# Schematic.net
KiCad netlist of a schematic drawn in EAGLE
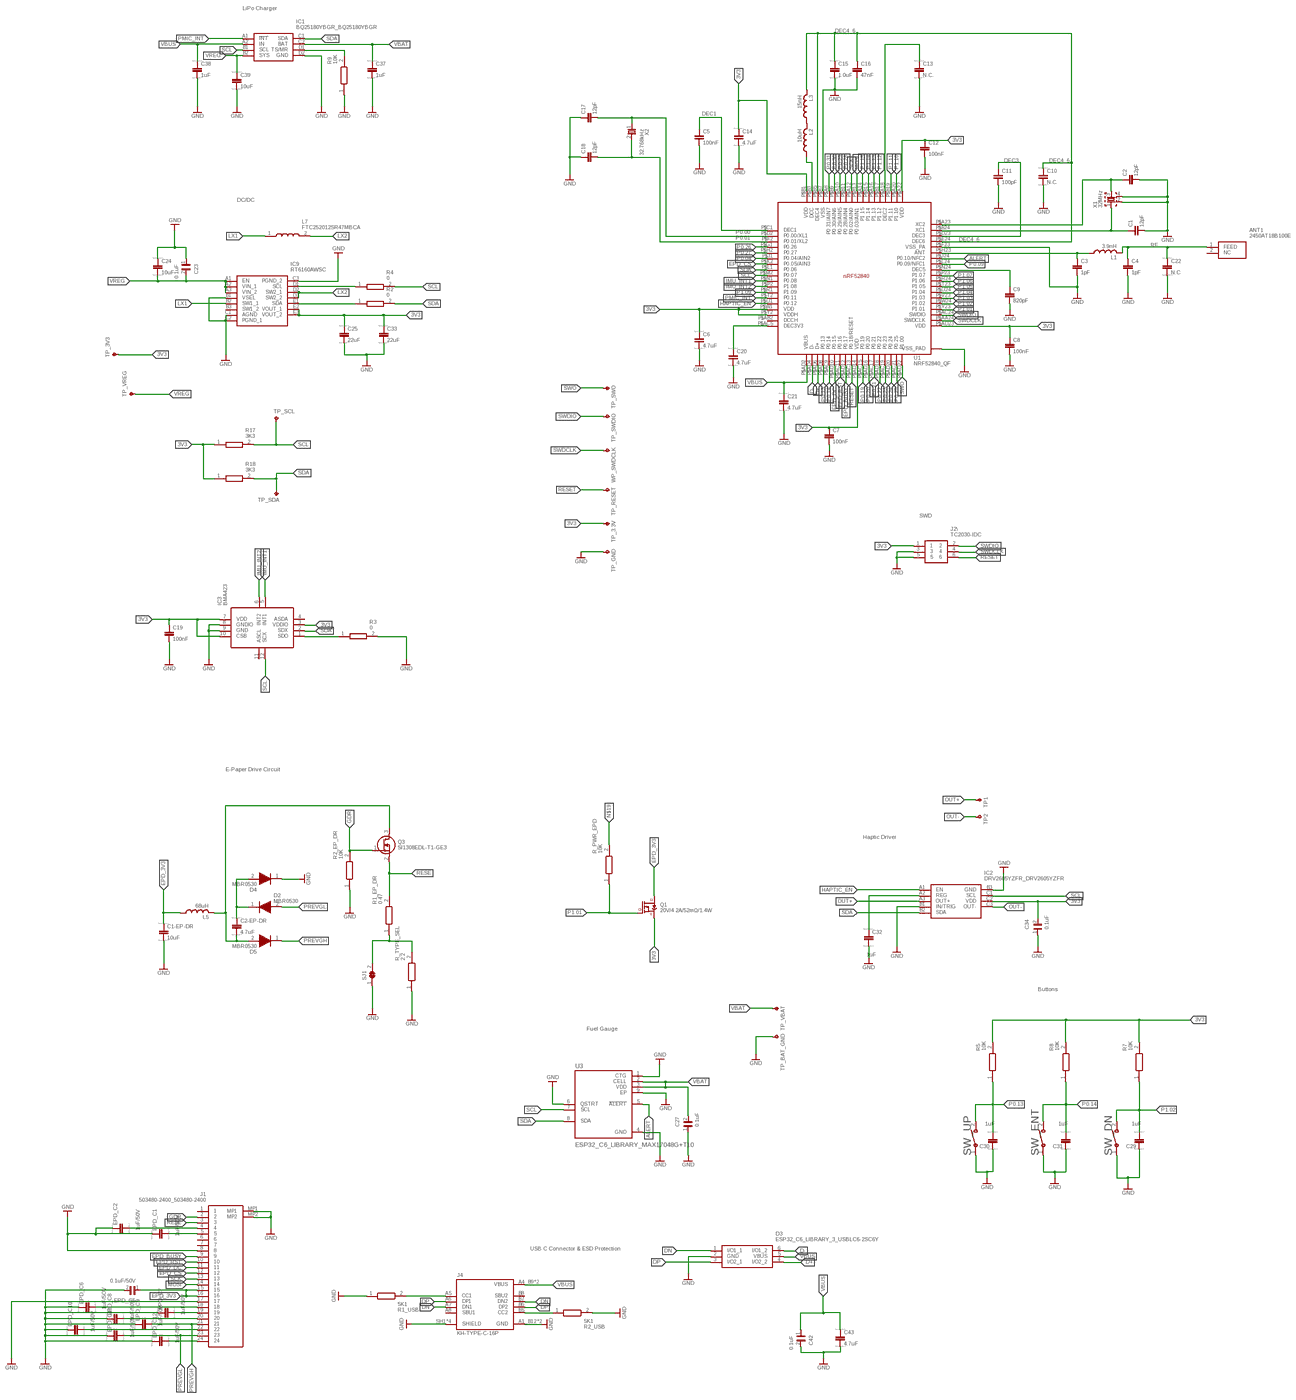
[diagram p0: schematic, sheet 1, overview]
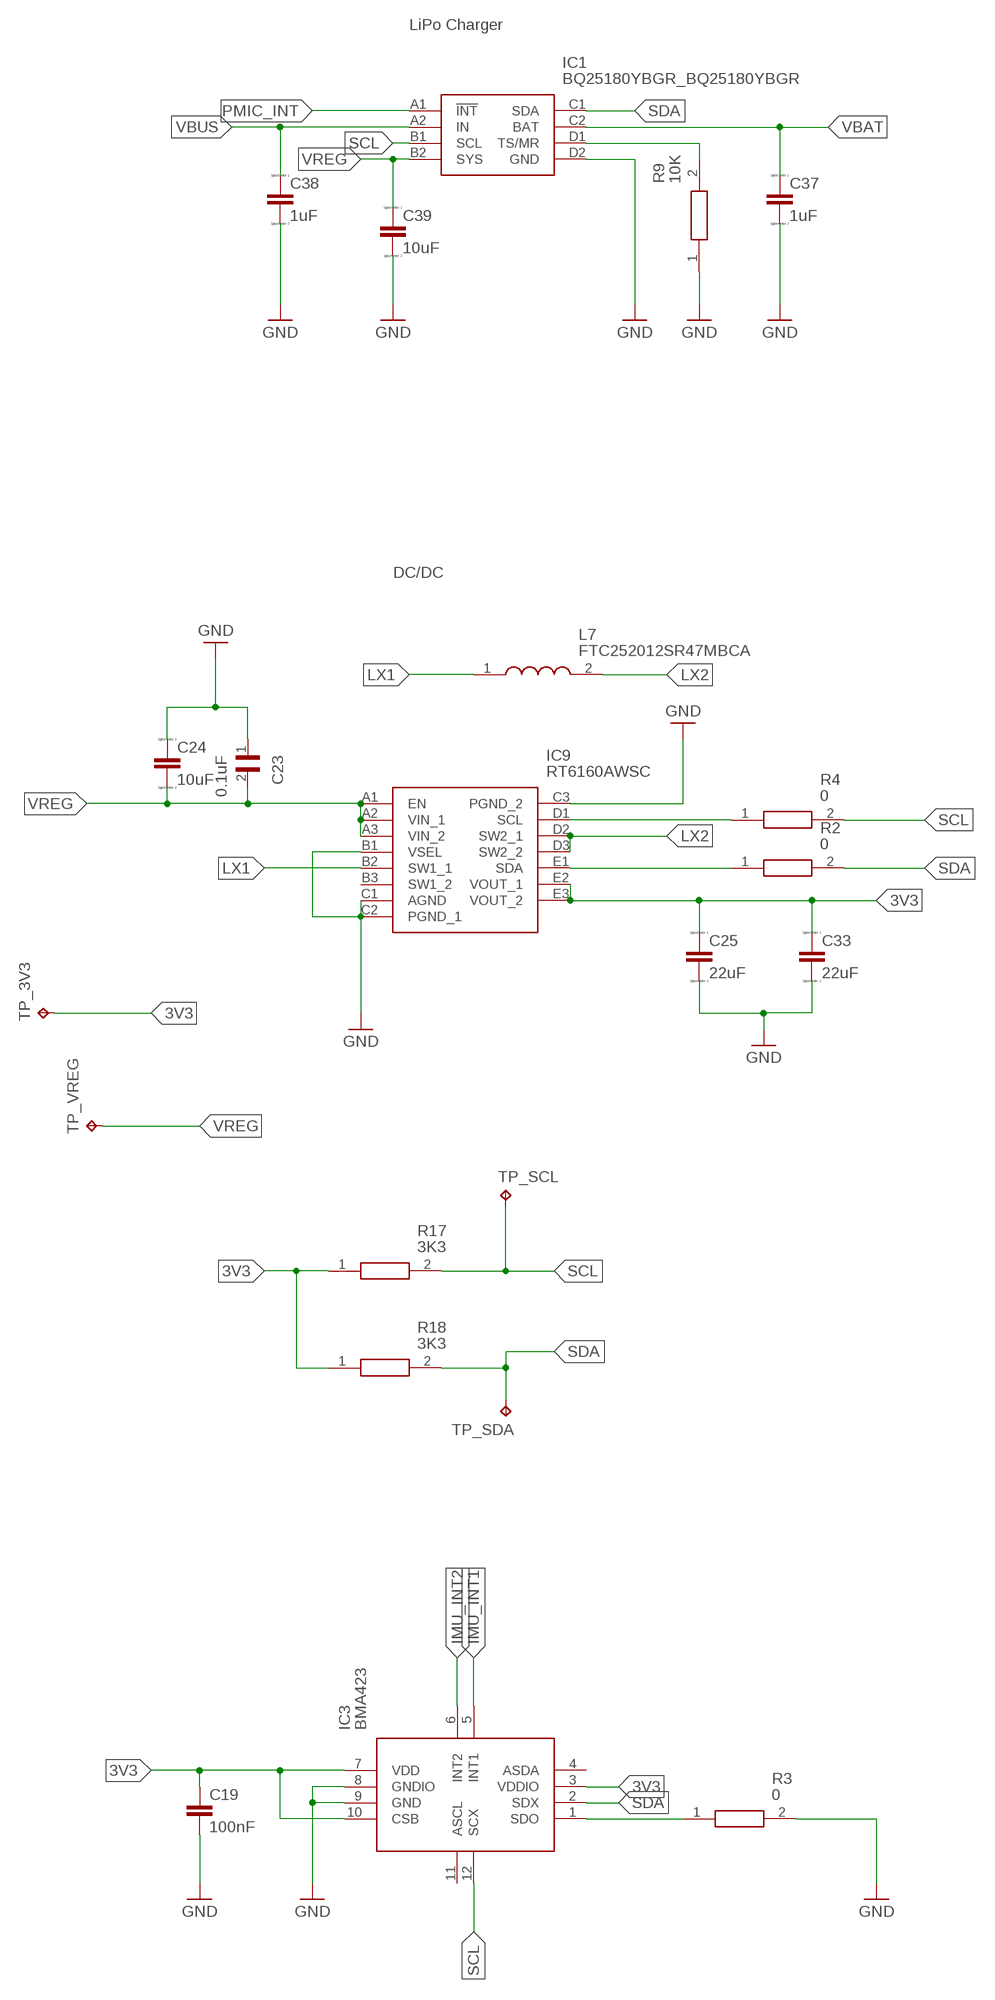
[diagram p1: schematic, sheet 1, part 1 of 4]
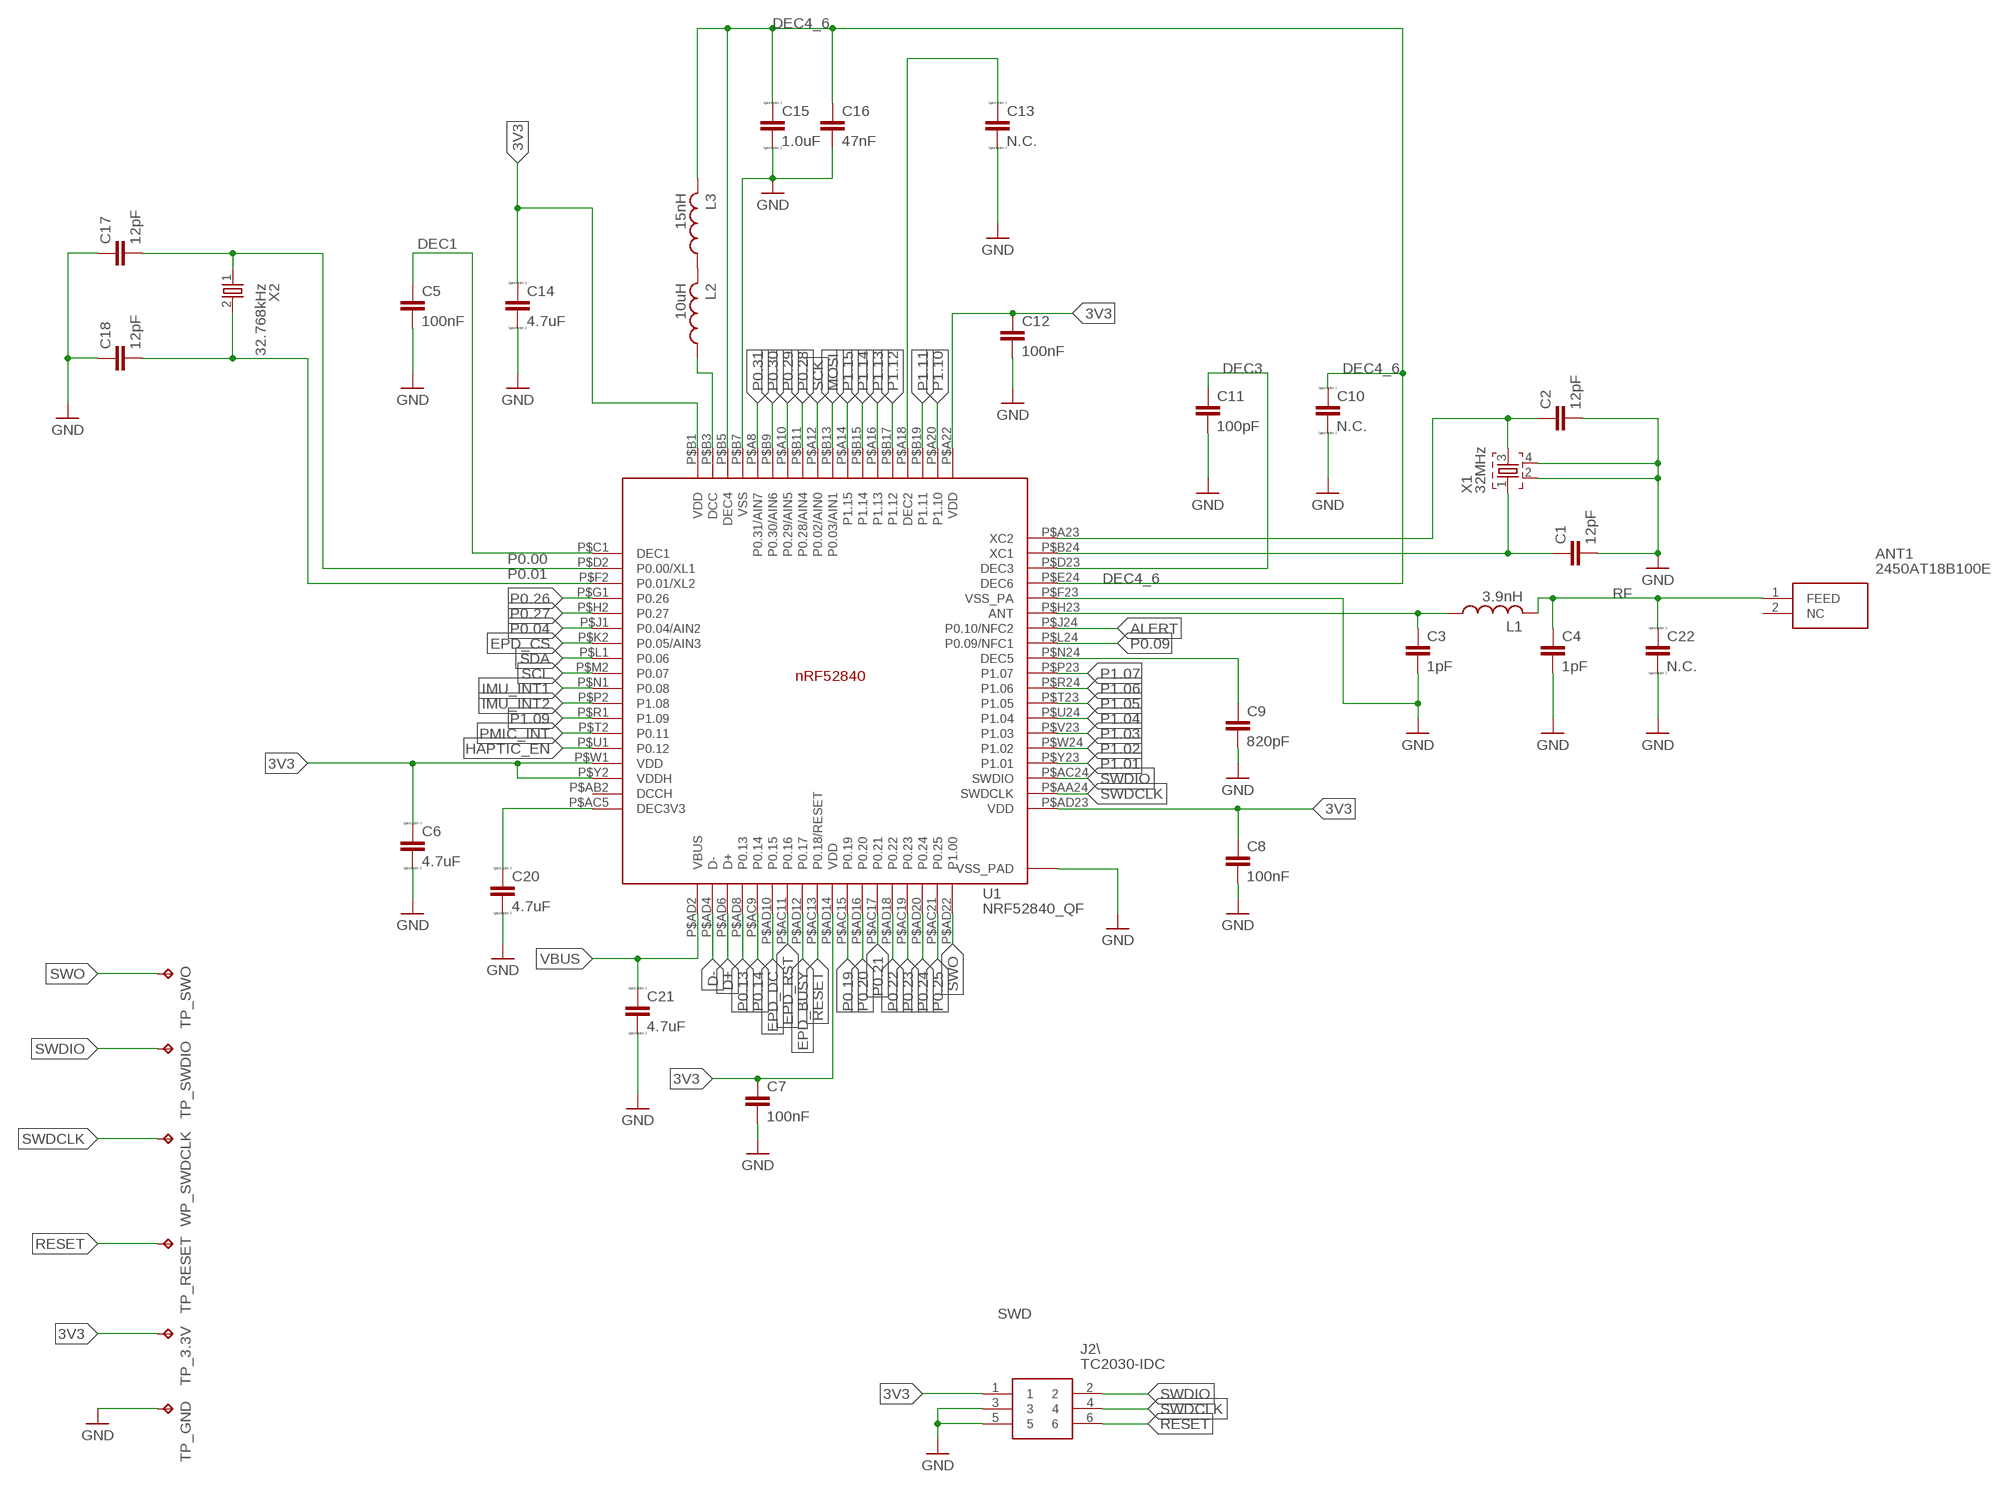
[diagram p2: schematic, sheet 1, part 2 of 4]
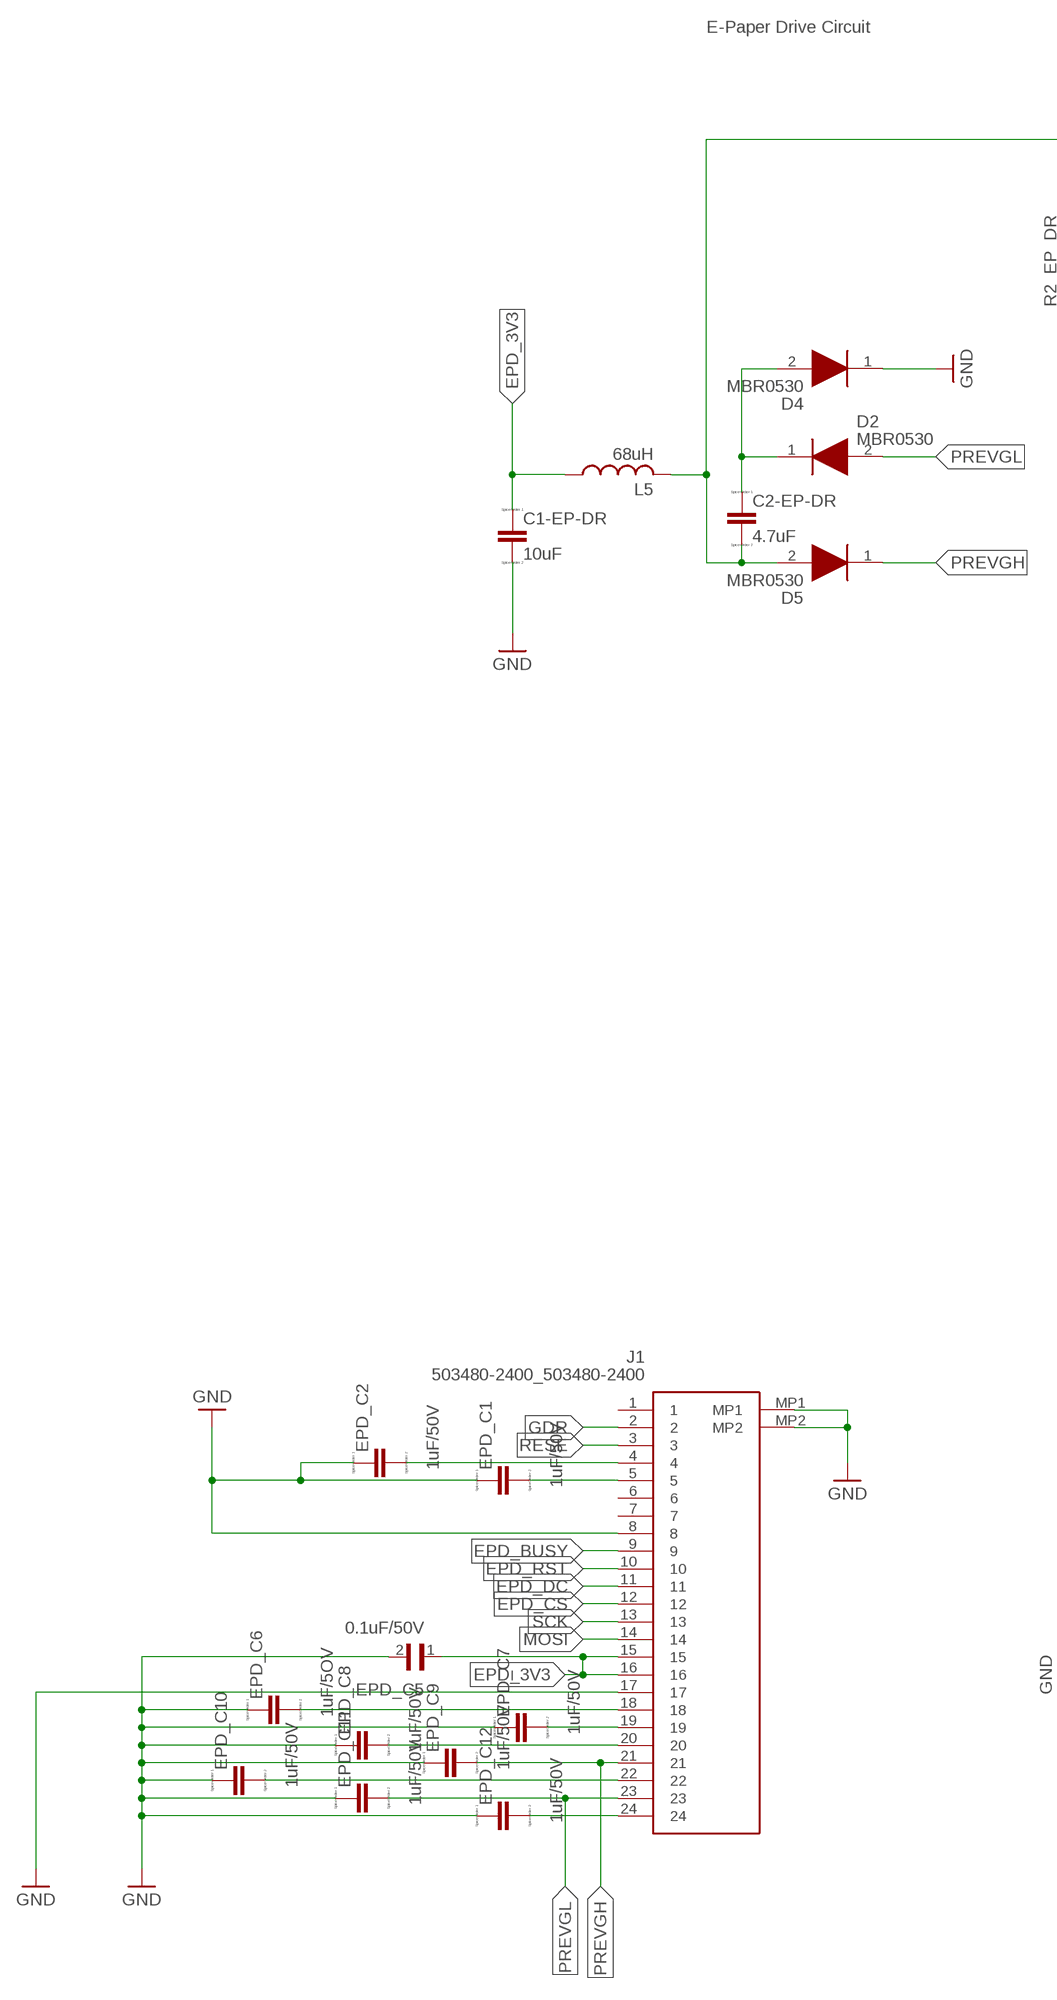
[diagram p3: schematic, sheet 1, part 3 of 4]
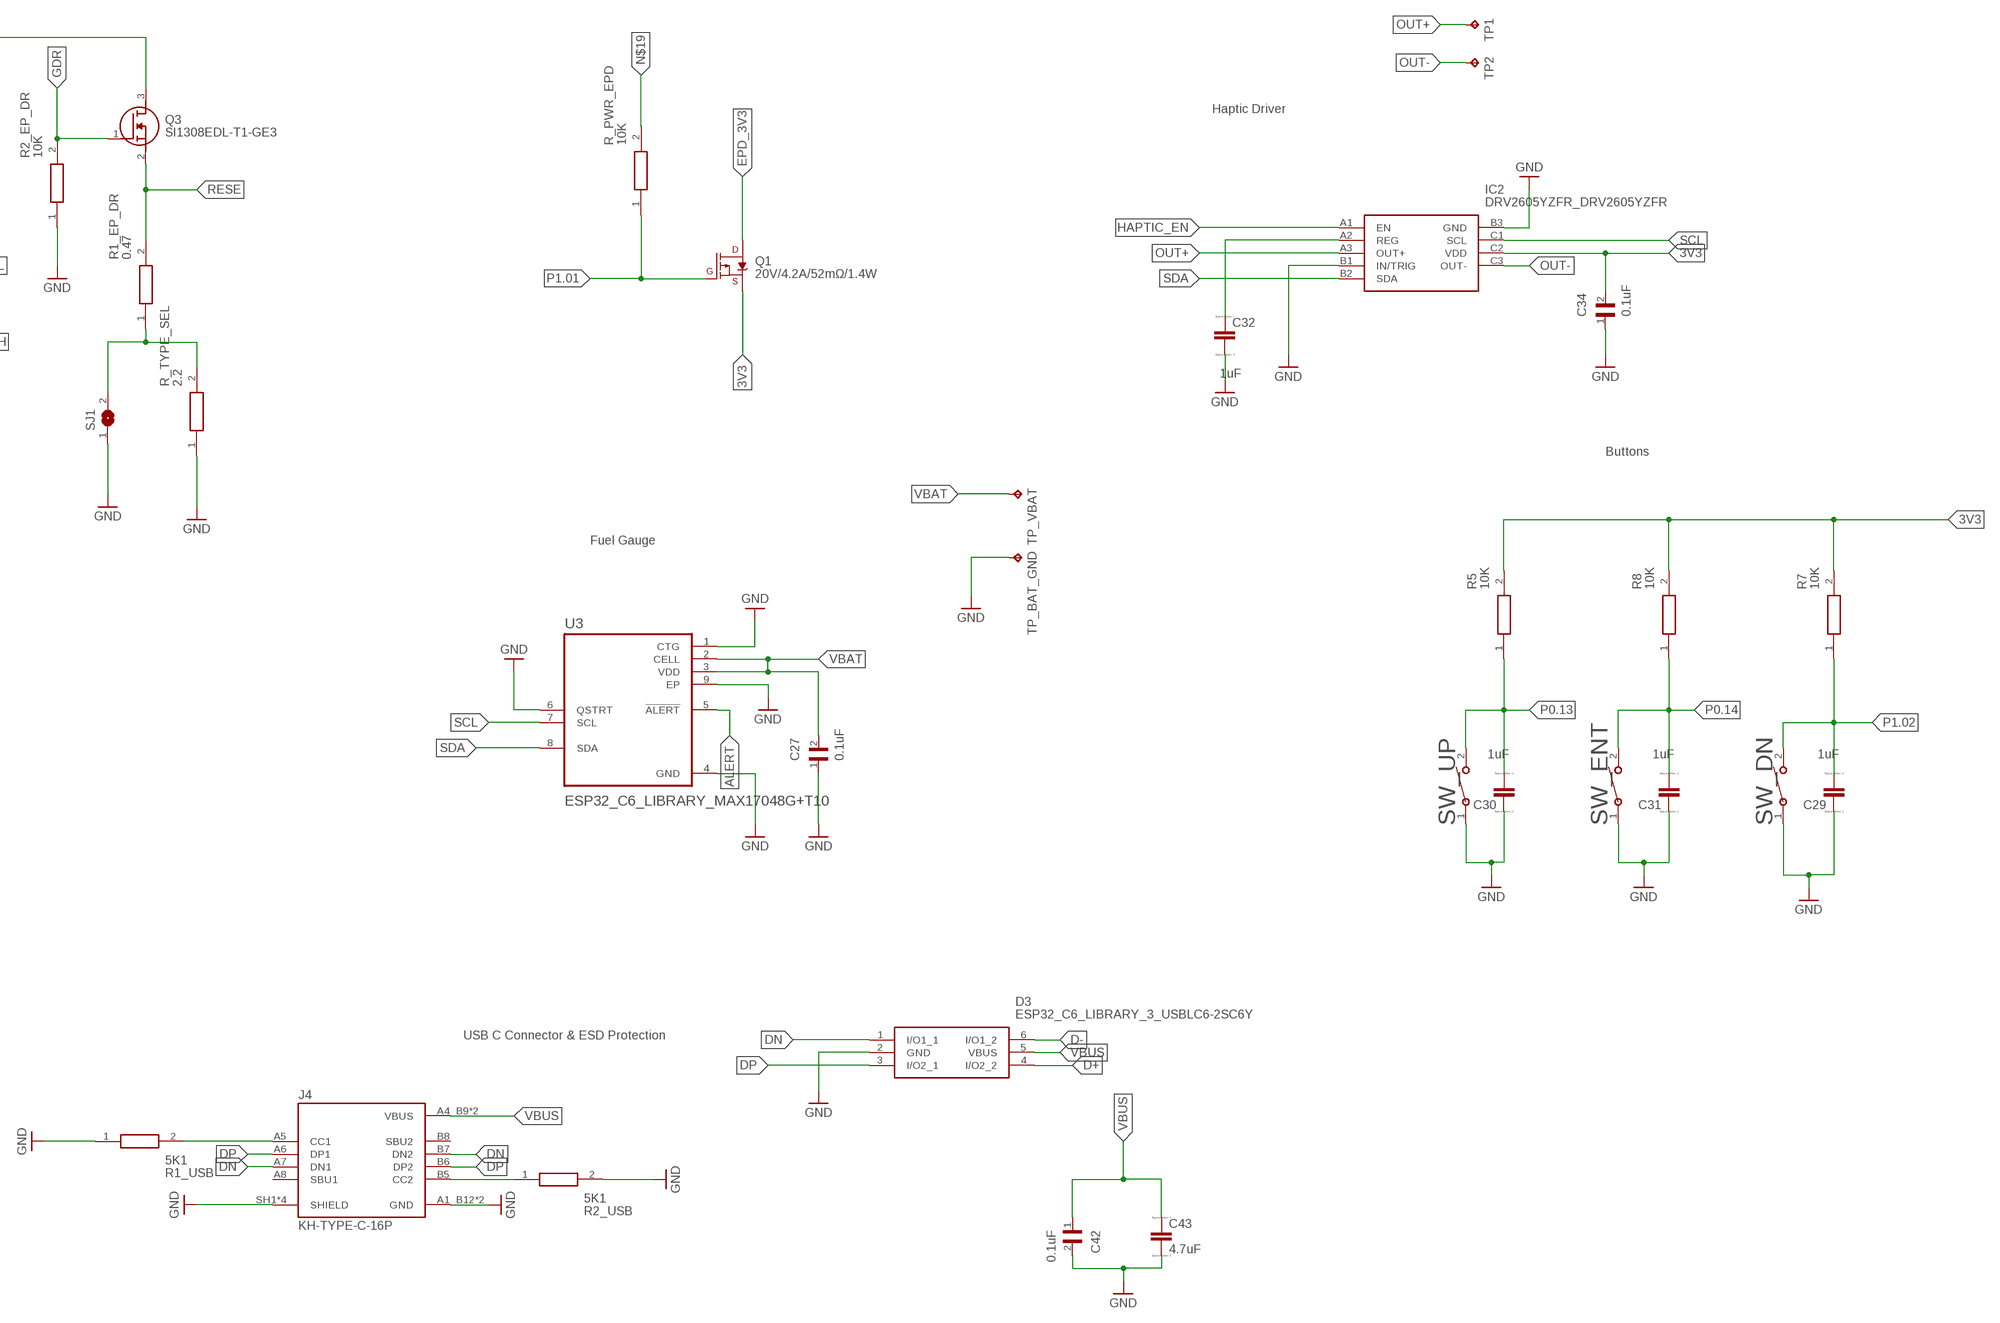
[diagram p4: schematic, sheet 1, part 4 of 4]

(export (version "E")
  (design (tool "Eeschema 10.0.6"))
  (components
    (comp (ref "ANT1")
      (value "2450AT18B100E")
      (footprint "eagle-import:2450AT18B100E_ANTC3216X140N")
      (fields (field (name "MOUSER_PART_NUMBER") "609-2450AT18B100E") (field (name "SPICEPREFIX") "B"))
      (libsource (lib "eagle-import") (part "2450AT18B100E_2450AT18B100E"))
    )
    (comp (ref "C1")
      (value "12pF")
      (footprint "eagle-import:NORDIC_NRF_3_RESC0201_L")
      (libsource (lib "eagle-import") (part "NORDIC_NRF_3_CAPACITOR_0201_L"))
    )
    (comp (ref "C1-EP-DR")
      (value "10uF")
      (footprint "eagle-import:ESP32_C6_LIBRARY_1_ESP32_WROVER_EAGLE-LTSPICE_C0402")
      (libsource (lib "eagle-import") (part "ESP32_C6_LIBRARY_1_ESP32_WROVER_EAGLE-LTSPICE_CC0402"))
    )
    (comp (ref "C2")
      (value "12pF")
      (footprint "eagle-import:NORDIC_NRF_3_RESC0201_L")
      (libsource (lib "eagle-import") (part "NORDIC_NRF_3_CAPACITOR_0201_L"))
    )
    (comp (ref "C2-EP-DR")
      (value "4.7uF")
      (footprint "eagle-import:ESP32_C6_LIBRARY_1_ESP32_WROVER_EAGLE-LTSPICE_C0402")
      (libsource (lib "eagle-import") (part "ESP32_C6_LIBRARY_1_ESP32_WROVER_EAGLE-LTSPICE_CC0402"))
    )
    (comp (ref "C3")
      (value "1pF")
      (footprint "eagle-import:NORDIC_NRF_3_RESC0201_L")
      (libsource (lib "eagle-import") (part "NORDIC_NRF_3_CAPACITOR_0201_L"))
    )
    (comp (ref "C4")
      (value "1pF")
      (footprint "eagle-import:NORDIC_NRF_3_RESC0201_L")
      (libsource (lib "eagle-import") (part "NORDIC_NRF_3_CAPACITOR_0201_L"))
    )
    (comp (ref "C5")
      (value "100nF")
      (footprint "eagle-import:NORDIC_NRF_3_RESC0201_L")
      (libsource (lib "eagle-import") (part "NORDIC_NRF_3_CAPACITOR_0201_L"))
    )
    (comp (ref "C6")
      (value "4.7uF")
      (footprint "eagle-import:ESP32_C6_LIBRARY_1_ESP32_WROVER_EAGLE-LTSPICE_C0402")
      (libsource (lib "eagle-import") (part "ESP32_C6_LIBRARY_1_ESP32_WROVER_EAGLE-LTSPICE_CC0402"))
    )
    (comp (ref "C7")
      (value "100nF")
      (footprint "eagle-import:NORDIC_NRF_3_RESC0201_L")
      (libsource (lib "eagle-import") (part "NORDIC_NRF_3_CAPACITOR_0201_L"))
    )
    (comp (ref "C8")
      (value "100nF")
      (footprint "eagle-import:NORDIC_NRF_3_RESC0201_L")
      (libsource (lib "eagle-import") (part "NORDIC_NRF_3_CAPACITOR_0201_L"))
    )
    (comp (ref "C9")
      (value "820pF")
      (footprint "eagle-import:NORDIC_NRF_3_RESC0201_L")
      (libsource (lib "eagle-import") (part "NORDIC_NRF_3_CAPACITOR_0201_L"))
    )
    (comp (ref "C10")
      (value "N.C.")
      (footprint "eagle-import:ESP32_C6_LIBRARY_1_ESP32_WROVER_EAGLE-LTSPICE_C0402")
      (libsource (lib "eagle-import") (part "ESP32_C6_LIBRARY_1_ESP32_WROVER_EAGLE-LTSPICE_CC0402"))
    )
    (comp (ref "C11")
      (value "100pF")
      (footprint "eagle-import:NORDIC_NRF_3_RESC0201_L")
      (libsource (lib "eagle-import") (part "NORDIC_NRF_3_CAPACITOR_0201_L"))
    )
    (comp (ref "C12")
      (value "100nF")
      (footprint "eagle-import:NORDIC_NRF_3_RESC0201_L")
      (libsource (lib "eagle-import") (part "NORDIC_NRF_3_CAPACITOR_0201_L"))
    )
    (comp (ref "C13")
      (value "N.C.")
      (footprint "eagle-import:ESP32_C6_LIBRARY_1_ESP32_WROVER_EAGLE-LTSPICE_C0402")
      (libsource (lib "eagle-import") (part "ESP32_C6_LIBRARY_1_ESP32_WROVER_EAGLE-LTSPICE_CC0402"))
    )
    (comp (ref "C14")
      (value "4.7uF")
      (footprint "eagle-import:ESP32_C6_LIBRARY_1_ESP32_WROVER_EAGLE-LTSPICE_C0402")
      (libsource (lib "eagle-import") (part "ESP32_C6_LIBRARY_1_ESP32_WROVER_EAGLE-LTSPICE_CC0402"))
    )
    (comp (ref "C15")
      (value "1.0uF")
      (footprint "eagle-import:ESP32_C6_LIBRARY_1_ESP32_WROVER_EAGLE-LTSPICE_C0402")
      (libsource (lib "eagle-import") (part "ESP32_C6_LIBRARY_1_ESP32_WROVER_EAGLE-LTSPICE_CC0402"))
    )
    (comp (ref "C16")
      (value "47nF")
      (footprint "eagle-import:NORDIC_NRF_3_RESC0201_L")
      (libsource (lib "eagle-import") (part "NORDIC_NRF_3_CAPACITOR_0201_L"))
    )
    (comp (ref "C17")
      (value "12pF")
      (footprint "eagle-import:NORDIC_NRF_3_RESC0201_L")
      (libsource (lib "eagle-import") (part "NORDIC_NRF_3_CAPACITOR_0201_L"))
    )
    (comp (ref "C18")
      (value "12pF")
      (footprint "eagle-import:NORDIC_NRF_3_RESC0201_L")
      (libsource (lib "eagle-import") (part "NORDIC_NRF_3_CAPACITOR_0201_L"))
    )
    (comp (ref "C19")
      (value "100nF")
      (footprint "eagle-import:NORDIC_NRF_3_RESC0201_L")
      (libsource (lib "eagle-import") (part "NORDIC_NRF_3_CAPACITOR_0201_L"))
    )
    (comp (ref "C20")
      (value "4.7uF")
      (footprint "eagle-import:ESP32_C6_LIBRARY_1_ESP32_WROVER_EAGLE-LTSPICE_C0402")
      (libsource (lib "eagle-import") (part "ESP32_C6_LIBRARY_1_ESP32_WROVER_EAGLE-LTSPICE_CC0402"))
    )
    (comp (ref "C21")
      (value "4.7uF")
      (footprint "eagle-import:ESP32_C6_LIBRARY_1_ESP32_WROVER_EAGLE-LTSPICE_C0402")
      (libsource (lib "eagle-import") (part "ESP32_C6_LIBRARY_1_ESP32_WROVER_EAGLE-LTSPICE_CC0402"))
    )
    (comp (ref "C22")
      (value "N.C.")
      (footprint "eagle-import:ESP32_C6_LIBRARY_1_ESP32_WROVER_EAGLE-LTSPICE_C0402")
      (libsource (lib "eagle-import") (part "ESP32_C6_LIBRARY_1_ESP32_WROVER_EAGLE-LTSPICE_CC0402"))
    )
    (comp (ref "C23")
      (value "0.1uF")
      (footprint "eagle-import:GRM011R60J152KE01L_2_CAPC0201X13N")
      (fields (field (name "MF") "Murata") (field (name "MP") "GRM011R60J152KE01L"))
      (libsource (lib "eagle-import") (part "GRM011R60J152KE01L_2_GRM011R60J152KE01L"))
    )
    (comp (ref "C24")
      (value "10uF")
      (footprint "eagle-import:ESP32_C6_LIBRARY_1_ESP32_WROVER_EAGLE-LTSPICE_C0402")
      (libsource (lib "eagle-import") (part "ESP32_C6_LIBRARY_1_ESP32_WROVER_EAGLE-LTSPICE_CC0402"))
    )
    (comp (ref "C25")
      (value "22uF")
      (footprint "eagle-import:ESP32_C6_LIBRARY_1_ESP32_WROVER_EAGLE-LTSPICE_C0402")
      (libsource (lib "eagle-import") (part "ESP32_C6_LIBRARY_1_ESP32_WROVER_EAGLE-LTSPICE_CC0402"))
    )
    (comp (ref "C27")
      (value "0.1uF")
      (footprint "eagle-import:GRM011R60J152KE01L_2_CAPC0201X13N")
      (fields (field (name "MF") "Murata") (field (name "MP") "GRM011R60J152KE01L"))
      (libsource (lib "eagle-import") (part "GRM011R60J152KE01L_2_GRM011R60J152KE01L"))
    )
    (comp (ref "C29")
      (value "1uF")
      (footprint "eagle-import:ESP32_C6_LIBRARY_1_ESP32_WROVER_EAGLE-LTSPICE_C0402")
      (libsource (lib "eagle-import") (part "ESP32_C6_LIBRARY_1_ESP32_WROVER_EAGLE-LTSPICE_CC0402"))
    )
    (comp (ref "C30")
      (value "1uF")
      (footprint "eagle-import:ESP32_C6_LIBRARY_1_ESP32_WROVER_EAGLE-LTSPICE_C0402")
      (libsource (lib "eagle-import") (part "ESP32_C6_LIBRARY_1_ESP32_WROVER_EAGLE-LTSPICE_CC0402"))
    )
    (comp (ref "C31")
      (value "1uF")
      (footprint "eagle-import:ESP32_C6_LIBRARY_1_ESP32_WROVER_EAGLE-LTSPICE_C0402")
      (libsource (lib "eagle-import") (part "ESP32_C6_LIBRARY_1_ESP32_WROVER_EAGLE-LTSPICE_CC0402"))
    )
    (comp (ref "C32")
      (value "1uF")
      (footprint "eagle-import:ESP32_C6_LIBRARY_1_ESP32_WROVER_EAGLE-LTSPICE_C0402")
      (libsource (lib "eagle-import") (part "ESP32_C6_LIBRARY_1_ESP32_WROVER_EAGLE-LTSPICE_CC0402"))
    )
    (comp (ref "C33")
      (value "22uF")
      (footprint "eagle-import:ESP32_C6_LIBRARY_1_ESP32_WROVER_EAGLE-LTSPICE_C0402")
      (libsource (lib "eagle-import") (part "ESP32_C6_LIBRARY_1_ESP32_WROVER_EAGLE-LTSPICE_CC0402"))
    )
    (comp (ref "C34")
      (value "0.1uF")
      (footprint "eagle-import:GRM011R60J152KE01L_2_CAPC0201X13N")
      (fields (field (name "MF") "Murata") (field (name "MP") "GRM011R60J152KE01L"))
      (libsource (lib "eagle-import") (part "GRM011R60J152KE01L_2_GRM011R60J152KE01L"))
    )
    (comp (ref "C37")
      (value "1uF")
      (footprint "eagle-import:ESP32_C6_LIBRARY_1_ESP32_WROVER_EAGLE-LTSPICE_C0402")
      (libsource (lib "eagle-import") (part "ESP32_C6_LIBRARY_1_ESP32_WROVER_EAGLE-LTSPICE_CC0402"))
    )
    (comp (ref "C38")
      (value "1uF")
      (footprint "eagle-import:ESP32_C6_LIBRARY_1_ESP32_WROVER_EAGLE-LTSPICE_C0402")
      (libsource (lib "eagle-import") (part "ESP32_C6_LIBRARY_1_ESP32_WROVER_EAGLE-LTSPICE_CC0402"))
    )
    (comp (ref "C39")
      (value "10uF")
      (footprint "eagle-import:ESP32_C6_LIBRARY_1_ESP32_WROVER_EAGLE-LTSPICE_C0402")
      (libsource (lib "eagle-import") (part "ESP32_C6_LIBRARY_1_ESP32_WROVER_EAGLE-LTSPICE_CC0402"))
    )
    (comp (ref "C42")
      (value "0.1uF")
      (footprint "eagle-import:GRM011R60J152KE01L_2_CAPC0201X13N")
      (fields (field (name "MF") "Murata") (field (name "MP") "GRM011R60J152KE01L"))
      (libsource (lib "eagle-import") (part "GRM011R60J152KE01L_2_GRM011R60J152KE01L"))
    )
    (comp (ref "C43")
      (value "4.7uF")
      (footprint "eagle-import:ESP32_C6_LIBRARY_1_ESP32_WROVER_EAGLE-LTSPICE_C0402")
      (libsource (lib "eagle-import") (part "ESP32_C6_LIBRARY_1_ESP32_WROVER_EAGLE-LTSPICE_CC0402"))
    )
    (comp (ref "D2")
      (value "MBR0530")
      (footprint "eagle-import:ESP32_C6_LIBRARY_5_SOD3716X135N")
      (fields (field (name "MF") "ON Semiconductor"))
      (libsource (lib "eagle-import") (part "ESP32_C6_LIBRARY_5_MBR0530"))
    )
    (comp (ref "D3")
      (value "ESP32_C6_LIBRARY_3_USBLC6-2SC6Y")
      (footprint "eagle-import:ESP32_C6_LIBRARY_3_SOT95P280X145-6N")
      (fields (field (name "MF") "STMicroelectronics") (field (name "MP") "USBLC6-2SC6Y"))
      (libsource (lib "eagle-import") (part "ESP32_C6_LIBRARY_3_USBLC6-2SC6Y"))
    )
    (comp (ref "D4")
      (value "MBR0530")
      (footprint "eagle-import:ESP32_C6_LIBRARY_5_SOD3716X135N")
      (fields (field (name "MF") "ON Semiconductor"))
      (libsource (lib "eagle-import") (part "ESP32_C6_LIBRARY_5_MBR0530"))
    )
    (comp (ref "D5")
      (value "MBR0530")
      (footprint "eagle-import:ESP32_C6_LIBRARY_5_SOD3716X135N")
      (fields (field (name "MF") "ON Semiconductor"))
      (libsource (lib "eagle-import") (part "ESP32_C6_LIBRARY_5_MBR0530"))
    )
    (comp (ref "EPD_C1")
      (value "1uF/50V")
      (footprint "eagle-import:ESP32_C6_LIBRARY_1_ESP32_WROVER_EAGLE-LTSPICE_C0402")
      (libsource (lib "eagle-import") (part "ESP32_C6_LIBRARY_1_ESP32_WROVER_EAGLE-LTSPICE_CC0402"))
    )
    (comp (ref "EPD_C2")
      (value "1uF/50V")
      (footprint "eagle-import:ESP32_C6_LIBRARY_1_ESP32_WROVER_EAGLE-LTSPICE_C0402")
      (libsource (lib "eagle-import") (part "ESP32_C6_LIBRARY_1_ESP32_WROVER_EAGLE-LTSPICE_CC0402"))
    )
    (comp (ref "EPD_C5")
      (value "0.1uF/50V")
      (footprint "eagle-import:GRM011R60J152KE01L_2_CAPC0201X13N")
      (fields (field (name "MF") "Murata") (field (name "MP") "GRM011R60J152KE01L"))
      (libsource (lib "eagle-import") (part "GRM011R60J152KE01L_2_GRM011R60J152KE01L"))
    )
    (comp (ref "EPD_C6")
      (value "1uF/5OV")
      (footprint "eagle-import:ESP32_C6_LIBRARY_1_ESP32_WROVER_EAGLE-LTSPICE_C0402")
      (libsource (lib "eagle-import") (part "ESP32_C6_LIBRARY_1_ESP32_WROVER_EAGLE-LTSPICE_CC0402"))
    )
    (comp (ref "EPD_C7")
      (value "1uF/50V")
      (footprint "eagle-import:ESP32_C6_LIBRARY_1_ESP32_WROVER_EAGLE-LTSPICE_C0402")
      (libsource (lib "eagle-import") (part "ESP32_C6_LIBRARY_1_ESP32_WROVER_EAGLE-LTSPICE_CC0402"))
    )
    (comp (ref "EPD_C8")
      (value "1uF/50V")
      (footprint "eagle-import:ESP32_C6_LIBRARY_1_ESP32_WROVER_EAGLE-LTSPICE_C0402")
      (libsource (lib "eagle-import") (part "ESP32_C6_LIBRARY_1_ESP32_WROVER_EAGLE-LTSPICE_CC0402"))
    )
    (comp (ref "EPD_C9")
      (value "1uF/50V")
      (footprint "eagle-import:ESP32_C6_LIBRARY_1_ESP32_WROVER_EAGLE-LTSPICE_C0402")
      (libsource (lib "eagle-import") (part "ESP32_C6_LIBRARY_1_ESP32_WROVER_EAGLE-LTSPICE_CC0402"))
    )
    (comp (ref "EPD_C10")
      (value "1uF/50V")
      (footprint "eagle-import:ESP32_C6_LIBRARY_1_ESP32_WROVER_EAGLE-LTSPICE_C0402")
      (libsource (lib "eagle-import") (part "ESP32_C6_LIBRARY_1_ESP32_WROVER_EAGLE-LTSPICE_CC0402"))
    )
    (comp (ref "EPD_C11")
      (value "1uF/50V")
      (footprint "eagle-import:ESP32_C6_LIBRARY_1_ESP32_WROVER_EAGLE-LTSPICE_C0402")
      (libsource (lib "eagle-import") (part "ESP32_C6_LIBRARY_1_ESP32_WROVER_EAGLE-LTSPICE_CC0402"))
    )
    (comp (ref "EPD_C12")
      (value "1uF/50V")
      (footprint "eagle-import:ESP32_C6_LIBRARY_1_ESP32_WROVER_EAGLE-LTSPICE_C0402")
      (libsource (lib "eagle-import") (part "ESP32_C6_LIBRARY_1_ESP32_WROVER_EAGLE-LTSPICE_CC0402"))
    )
    (comp (ref "IC1")
      (value "BQ25180YBGR_BQ25180YBGR")
      (footprint "eagle-import:BQ25180YBGR_BGA8C40P2X4_100X155X50")
      (fields
        (field (name "ARROW_PART_NUMBER") "BQ25180YBGR")
        (field (name "MOUSER_PART_NUMBER") "595-BQ25180YBGR")
      )
      (libsource (lib "eagle-import") (part "BQ25180YBGR_BQ25180YBGR"))
    )
    (comp (ref "IC2")
      (value "DRV2605YZFR_DRV2605YZFR")
      (footprint "eagle-import:DRV2605YZFR_BGA9C50P3X3_144X144X62")
      (fields (field (name "ARROW_PART_NUMBER") "DRV2605YZFR"))
      (libsource (lib "eagle-import") (part "DRV2605YZFR_DRV2605YZFR"))
    )
    (comp (ref "IC3")
      (value "BMA423")
      (footprint "eagle-import:BMA423_BMA423")
      (fields (field (name "MOUSER_PART_NUMBER") "262-BMA423"))
      (libsource (lib "eagle-import") (part "BMA423_BMA423"))
    )
    (comp (ref "IC9")
      (value "RT6160AWSC")
      (footprint "eagle-import:RT6160AWSC_BGA15C40P3X5_140X230X60")
      (fields (field (name "MOUSER_PART_NUMBER") "835-RT6160AWSC"))
      (libsource (lib "eagle-import") (part "RT6160AWSC_RT6160AWSC"))
    )
    (comp (ref "J1")
      (value "503480-2400_503480-2400")
      (footprint "eagle-import:503480-2400_5034802400")
      (fields
        (field (name "MANUFACTURER_PART_NUMBER") "503480-2400")
        (field (name "MOUSER_PART_NUMBER") "538-503480-2400")
      )
      (libsource (lib "eagle-import") (part "503480-2400_503480-2400"))
    )
    (comp (ref "J2\\")
      (value "TC2030-IDC")
      (footprint "eagle-import:TC2030-IDC_TC2030IDC")
      (libsource (lib "eagle-import") (part "TC2030-IDC_TC2030-IDC"))
    )
    (comp (ref "J4")
      (value "KH-TYPE-C-16P")
      (footprint "eagle-import:KH-TYPE-C-16P_KINGHELM_KH-TYPE-C-16P")
      (fields (field (name "MF") "kinghelm"))
      (libsource (lib "eagle-import") (part "KH-TYPE-C-16P_KH-TYPE-C-16P"))
    )
    (comp (ref "L1")
      (value "3.9nH")
      (footprint "eagle-import:NORDIC_NRF_2_RESC0402_L")
      (libsource (lib "eagle-import") (part "NORDIC_NRF_2_INDUCTOR_0402_L"))
    )
    (comp (ref "L2")
      (value "10uH")
      (footprint "eagle-import:NORDIC_NRF_2_RESC0402_L")
      (libsource (lib "eagle-import") (part "NORDIC_NRF_2_INDUCTOR_0402_L"))
    )
    (comp (ref "L3")
      (value "15nH")
      (footprint "eagle-import:NORDIC_NRF_2_RESC0402_L")
      (libsource (lib "eagle-import") (part "NORDIC_NRF_2_INDUCTOR_0402_L"))
    )
    (comp (ref "L5")
      (value "68uH")
      (footprint "eagle-import:NORDIC_NRF_2_RESC0402_L")
      (libsource (lib "eagle-import") (part "NORDIC_NRF_2_INDUCTOR_0402_L"))
    )
    (comp (ref "L7")
      (value "FTC252012SR47MBCA")
      (footprint "eagle-import:MLP2016SR47MT0S1_INDC2016X100N")
      (libsource (lib "eagle-import") (part "MLP2016SR47MT0S1_FTC252012SR47MBCA"))
    )
    (comp (ref "Q1")
      (value "20V/4.2A/52mΩ/1.4W")
      (footprint "eagle-import:ESP32_C6_LIBRARY_4_ESP32_C6_LIBRARY_4_ESP32_C6_LIBRARY_4_ESP32_C6_LIBRARY_4_ESP32_WROVER_SPARKFUN-DISCRETESEMI_SOT23-3")
      (libsource (lib "eagle-import") (part "ESP32_C6_LIBRARY_4_ESP32_WROVER_SPARKFUN-DISCRETESEMI_MOSFET_PCH-DMG2305UX-7"))
    )
    (comp (ref "Q3")
      (value "SI1308EDL-T1-GE3")
      (footprint "eagle-import:ESP32_C6_LIBRARY_6_SOT65P210X110-3N")
      (fields (field (name "MF") "Vishay Siliconix"))
      (libsource (lib "eagle-import") (part "ESP32_C6_LIBRARY_6_SI1308EDL-T1-GE3"))
    )
    (comp (ref "R1_EP_DR")
      (value "0.47")
      (footprint "eagle-import:CPF0201D7K68C1_0201")
      (libsource (lib "eagle-import") (part "CPF0201D7K68C1_CPF0201D7K68C1"))
    )
    (comp (ref "R1_USB")
      (value "5K1")
      (footprint "eagle-import:CPF0201D7K68C1_0201")
      (libsource (lib "eagle-import") (part "CPF0201D7K68C1_CPF0201D7K68C1"))
    )
    (comp (ref "R2")
      (value "0")
      (footprint "eagle-import:CPF0201D7K68C1_0201")
      (libsource (lib "eagle-import") (part "CPF0201D7K68C1_CPF0201D7K68C1"))
    )
    (comp (ref "R2_EP_DR")
      (value "10K")
      (footprint "eagle-import:CPF0201D7K68C1_0201")
      (libsource (lib "eagle-import") (part "CPF0201D7K68C1_CPF0201D7K68C1"))
    )
    (comp (ref "R2_USB")
      (value "5K1")
      (footprint "eagle-import:CPF0201D7K68C1_0201")
      (libsource (lib "eagle-import") (part "CPF0201D7K68C1_CPF0201D7K68C1"))
    )
    (comp (ref "R3")
      (value "0")
      (footprint "eagle-import:CPF0201D7K68C1_0201")
      (libsource (lib "eagle-import") (part "CPF0201D7K68C1_CPF0201D7K68C1"))
    )
    (comp (ref "R4")
      (value "0")
      (footprint "eagle-import:CPF0201D7K68C1_0201")
      (libsource (lib "eagle-import") (part "CPF0201D7K68C1_CPF0201D7K68C1"))
    )
    (comp (ref "R5")
      (value "10K")
      (footprint "eagle-import:CPF0201D7K68C1_0201")
      (libsource (lib "eagle-import") (part "CPF0201D7K68C1_CPF0201D7K68C1"))
    )
    (comp (ref "R7")
      (value "10K")
      (footprint "eagle-import:CPF0201D7K68C1_0201")
      (libsource (lib "eagle-import") (part "CPF0201D7K68C1_CPF0201D7K68C1"))
    )
    (comp (ref "R8")
      (value "10K")
      (footprint "eagle-import:CPF0201D7K68C1_0201")
      (libsource (lib "eagle-import") (part "CPF0201D7K68C1_CPF0201D7K68C1"))
    )
    (comp (ref "R9")
      (value "10K")
      (footprint "eagle-import:CPF0201D7K68C1_0201")
      (libsource (lib "eagle-import") (part "CPF0201D7K68C1_CPF0201D7K68C1"))
    )
    (comp (ref "R17")
      (value "3K3")
      (footprint "eagle-import:CPF0201D7K68C1_0201")
      (libsource (lib "eagle-import") (part "CPF0201D7K68C1_CPF0201D7K68C1"))
    )
    (comp (ref "R18")
      (value "3K3")
      (footprint "eagle-import:CPF0201D7K68C1_0201")
      (libsource (lib "eagle-import") (part "CPF0201D7K68C1_CPF0201D7K68C1"))
    )
    (comp (ref "R_PWR_EPD")
      (value "10K")
      (footprint "eagle-import:CPF0201D7K68C1_0201")
      (libsource (lib "eagle-import") (part "CPF0201D7K68C1_CPF0201D7K68C1"))
    )
    (comp (ref "R_TYPE_SEL")
      (value "2.2")
      (footprint "eagle-import:CPF0201D7K68C1_0201")
      (libsource (lib "eagle-import") (part "CPF0201D7K68C1_CPF0201D7K68C1"))
    )
    (comp (ref "SJ1")
      (value "SJ")
      (footprint "eagle-import:ESP32_C6_LIBRARY_7_JUMPER_SJ")
      (libsource (lib "eagle-import") (part "ESP32_C6_LIBRARY_7_JUMPER_SJ"))
    )
    (comp (ref "SW_DN")
      (value "2025-10-22_07-23-44_LIBRARY_EVP-AKE31ASW_EVP-AKE31A_PAN")
      (footprint "eagle-import:2025-10-22_07-23-44_LIBRARY_SW_EVP-AKE31A_PAN")
      (fields
        (field (name "MANUFACTURER_PART_NUMBER") "EVP-AKE31A")
        (field (name "COPYRIGHT") "Copyright (C) 2025 Ultra Librarian. All rights reserved.")
      )
      (libsource (lib "eagle-import") (part "2025-10-22_07-23-44_LIBRARY_EVP-AKE31ASW_EVP-AKE31A_PAN"))
    )
    (comp (ref "SW_ENT")
      (value "2025-10-22_07-23-44_LIBRARY_EVP-AKE31ASW_EVP-AKE31A_PAN")
      (footprint "eagle-import:2025-10-22_07-23-44_LIBRARY_SW_EVP-AKE31A_PAN")
      (fields
        (field (name "MANUFACTURER_PART_NUMBER") "EVP-AKE31A")
        (field (name "COPYRIGHT") "Copyright (C) 2025 Ultra Librarian. All rights reserved.")
      )
      (libsource (lib "eagle-import") (part "2025-10-22_07-23-44_LIBRARY_EVP-AKE31ASW_EVP-AKE31A_PAN"))
    )
    (comp (ref "SW_UP")
      (value "2025-10-22_07-23-44_LIBRARY_EVP-AKE31ASW_EVP-AKE31A_PAN")
      (footprint "eagle-import:2025-10-22_07-23-44_LIBRARY_SW_EVP-AKE31A_PAN")
      (fields
        (field (name "MANUFACTURER_PART_NUMBER") "EVP-AKE31A")
        (field (name "COPYRIGHT") "Copyright (C) 2025 Ultra Librarian. All rights reserved.")
      )
      (libsource (lib "eagle-import") (part "2025-10-22_07-23-44_LIBRARY_EVP-AKE31ASW_EVP-AKE31A_PAN"))
    )
    (comp (ref "TP1")
      (value "HECTOR_WATCH_1_TPTP20R")
      (footprint "eagle-import:HECTOR_WATCH_1_TP20R")
      (libsource (lib "eagle-import") (part "HECTOR_WATCH_1_TPTP20R"))
    )
    (comp (ref "TP2")
      (value "HECTOR_WATCH_1_TPTP20R")
      (footprint "eagle-import:HECTOR_WATCH_1_TP20R")
      (libsource (lib "eagle-import") (part "HECTOR_WATCH_1_TPTP20R"))
    )
    (comp (ref "TP_3.3V")
      (value "HECTOR_WATCH_1_TPTP20R")
      (footprint "eagle-import:HECTOR_WATCH_1_TP20R")
      (libsource (lib "eagle-import") (part "HECTOR_WATCH_1_TPTP20R"))
    )
    (comp (ref "TP_3V3")
      (value "HECTOR_WATCH_1_TPTP20R")
      (footprint "eagle-import:HECTOR_WATCH_1_TP20R")
      (libsource (lib "eagle-import") (part "HECTOR_WATCH_1_TPTP20R"))
    )
    (comp (ref "TP_BAT_GND")
      (value "HECTOR_WATCH_1_TPTP20R")
      (footprint "eagle-import:HECTOR_WATCH_1_TP20R")
      (libsource (lib "eagle-import") (part "HECTOR_WATCH_1_TPTP20R"))
    )
    (comp (ref "TP_GND")
      (value "HECTOR_WATCH_1_TPTP20R")
      (footprint "eagle-import:HECTOR_WATCH_1_TP20R")
      (libsource (lib "eagle-import") (part "HECTOR_WATCH_1_TPTP20R"))
    )
    (comp (ref "TP_RESET")
      (value "HECTOR_WATCH_1_TPTP20R")
      (footprint "eagle-import:HECTOR_WATCH_1_TP20R")
      (libsource (lib "eagle-import") (part "HECTOR_WATCH_1_TPTP20R"))
    )
    (comp (ref "TP_SCL")
      (value "HECTOR_WATCH_1_TPTP20R")
      (footprint "eagle-import:HECTOR_WATCH_1_TP20R")
      (libsource (lib "eagle-import") (part "HECTOR_WATCH_1_TPTP20R"))
    )
    (comp (ref "TP_SDA")
      (value "HECTOR_WATCH_1_TPTP20R")
      (footprint "eagle-import:HECTOR_WATCH_1_TP20R")
      (libsource (lib "eagle-import") (part "HECTOR_WATCH_1_TPTP20R"))
    )
    (comp (ref "TP_SWDIO")
      (value "HECTOR_WATCH_1_TPTP20R")
      (footprint "eagle-import:HECTOR_WATCH_1_TP20R")
      (libsource (lib "eagle-import") (part "HECTOR_WATCH_1_TPTP20R"))
    )
    (comp (ref "TP_SWO")
      (value "HECTOR_WATCH_1_TPTP20R")
      (footprint "eagle-import:HECTOR_WATCH_1_TP20R")
      (libsource (lib "eagle-import") (part "HECTOR_WATCH_1_TPTP20R"))
    )
    (comp (ref "TP_VBAT")
      (value "HECTOR_WATCH_1_TPTP20R")
      (footprint "eagle-import:HECTOR_WATCH_1_TP20R")
      (libsource (lib "eagle-import") (part "HECTOR_WATCH_1_TPTP20R"))
    )
    (comp (ref "TP_VREG")
      (value "HECTOR_WATCH_1_TPTP20R")
      (footprint "eagle-import:HECTOR_WATCH_1_TP20R")
      (libsource (lib "eagle-import") (part "HECTOR_WATCH_1_TPTP20R"))
    )
    (comp (ref "U1")
      (value "NRF52840_QF")
      (footprint "eagle-import:NORDIC_NRF_4_AQFN50P700X700X85_HS-74N")
      (libsource (lib "eagle-import") (part "NORDIC_NRF_4_NRF52840_QF"))
    )
    (comp (ref "U3")
      (value "ESP32_C6_LIBRARY_MAX17048G+T10")
      (footprint "eagle-import:ESP32_C6_LIBRARY_SON50P200X200X80-9N")
      (fields (field (name "MF") "Analog Devices") (field (name "MP") "MAX17048G+T10"))
      (libsource (lib "eagle-import") (part "ESP32_C6_LIBRARY_MAX17048G+T10"))
    )
    (comp (ref "WP_SWDCLK")
      (value "HECTOR_WATCH_1_TPTP20R")
      (footprint "eagle-import:HECTOR_WATCH_1_TP20R")
      (libsource (lib "eagle-import") (part "HECTOR_WATCH_1_TPTP20R"))
    )
    (comp (ref "X1")
      (value "32MHz")
      (footprint "eagle-import:NORDIC_NRF_BT-XTAL_2016_N")
      (libsource (lib "eagle-import") (part "NORDIC_NRF_XTAL_32MHZ"))
    )
    (comp (ref "X2")
      (value "32.768kHz")
      (footprint "eagle-import:NORDIC_NRF_1_XTAL_3215_N")
      (libsource (lib "eagle-import") (part "NORDIC_NRF_1_XTAL_32KHZ"))
    )
  )
  (nets
    (net (code "1") (name "/DEC1") (class "Default")
      (node (ref "C5") (pin "1") (pinfunction "1_1") (pintype "passive"))
      (node (ref "U1") (pin "P$C1") (pinfunction "DEC1_P$C1") (pintype "power_in"))
    )
    (net (code "2") (name "/DEC3") (class "Default")
      (node (ref "C11") (pin "1") (pinfunction "1_1") (pintype "passive"))
      (node (ref "U1") (pin "P$D23") (pinfunction "DEC3_P$D23") (pintype "bidirectional"))
    )
    (net (code "3") (name "/DEC4_6") (class "Default")
      (node (ref "C10") (pin "1") (pinfunction "1_1") (pintype "passive"))
      (node (ref "C15") (pin "1") (pinfunction "1_1") (pintype "passive"))
      (node (ref "C16") (pin "1") (pinfunction "1_1") (pintype "passive"))
      (node (ref "L3") (pin "2") (pinfunction "2_2") (pintype "passive"))
      (node (ref "U1") (pin "P$B5") (pinfunction "DEC4_P$B5") (pintype "power_in"))
      (node (ref "U1") (pin "P$E24") (pinfunction "DEC6_P$E24") (pintype "bidirectional"))
    )
    (net (code "4") (name "/P0.00") (class "Default")
      (node (ref "C17") (pin "2") (pinfunction "2_2") (pintype "passive"))
      (node (ref "U1") (pin "P$D2") (pinfunction "P0.00/XL1_P$D2") (pintype "bidirectional"))
      (node (ref "X2") (pin "1") (pinfunction "1_1") (pintype "passive"))
    )
    (net (code "5") (name "/P0.01") (class "Default")
      (node (ref "C18") (pin "2") (pinfunction "2_2") (pintype "passive"))
      (node (ref "U1") (pin "P$F2") (pinfunction "P0.01/XL2_P$F2") (pintype "bidirectional"))
      (node (ref "X2") (pin "2") (pinfunction "2_2") (pintype "passive"))
    )
    (net (code "6") (name "/RF") (class "Default")
      (node (ref "ANT1") (pin "1") (pinfunction "FEED_1") (pintype "input"))
      (node (ref "C22") (pin "1") (pinfunction "1_1") (pintype "passive"))
      (node (ref "C4") (pin "1") (pinfunction "1_1") (pintype "passive"))
      (node (ref "L1") (pin "2") (pinfunction "2_2") (pintype "passive"))
    )
    (net (code "7") (name "3V3") (class "Default")
      (node (ref "C12") (pin "1") (pinfunction "1_1") (pintype "passive"))
      (node (ref "C14") (pin "1") (pinfunction "1_1") (pintype "passive"))
      (node (ref "C19") (pin "1") (pinfunction "1_1") (pintype "passive"))
      (node (ref "C25") (pin "1") (pinfunction "1_1") (pintype "passive"))
      (node (ref "C33") (pin "1") (pinfunction "1_1") (pintype "passive"))
      (node (ref "C34") (pin "2") (pinfunction "2_2") (pintype "passive"))
      (node (ref "C6") (pin "1") (pinfunction "1_1") (pintype "passive"))
      (node (ref "C7") (pin "1") (pinfunction "1_1") (pintype "passive"))
      (node (ref "C8") (pin "1") (pinfunction "1_1") (pintype "passive"))
      (node (ref "IC2") (pin "C2") (pinfunction "VDD_C2") (pintype "bidirectional"))
      (node (ref "IC3") (pin "10") (pinfunction "CSB_10") (pintype "bidirectional"))
      (node (ref "IC3") (pin "3") (pinfunction "VDDIO_3") (pintype "bidirectional"))
      (node (ref "IC3") (pin "7") (pinfunction "VDD_7") (pintype "bidirectional"))
      (node (ref "IC9") (pin "E2") (pinfunction "VOUT_1_E2") (pintype "bidirectional"))
      (node (ref "IC9") (pin "E3") (pinfunction "VOUT_2_E3") (pintype "bidirectional"))
      (node (ref "J2\\") (pin "1") (pinfunction "1_1") (pintype "bidirectional"))
      (node (ref "Q1") (pin "2") (pinfunction "S_2") (pintype "bidirectional"))
      (node (ref "R17") (pin "1") (pinfunction "1_1") (pintype "bidirectional"))
      (node (ref "R18") (pin "1") (pinfunction "1_1") (pintype "bidirectional"))
      (node (ref "R5") (pin "2") (pinfunction "2_2") (pintype "bidirectional"))
      (node (ref "R7") (pin "2") (pinfunction "2_2") (pintype "bidirectional"))
      (node (ref "R8") (pin "2") (pinfunction "2_2") (pintype "bidirectional"))
      (node (ref "TP_3.3V") (pin "TP") (pinfunction "TP_TP") (pintype "input"))
      (node (ref "TP_3V3") (pin "TP") (pinfunction "TP_TP") (pintype "input"))
      (node (ref "U1") (pin "P$A22") (pinfunction "VDD_P$A22") (pintype "power_in"))
      (node (ref "U1") (pin "P$AD14") (pinfunction "VDD_P$AD14") (pintype "power_in"))
      (node (ref "U1") (pin "P$AD23") (pinfunction "VDD_P$AD23") (pintype "power_in"))
      (node (ref "U1") (pin "P$B1") (pinfunction "VDD_P$B1") (pintype "power_in"))
      (node (ref "U1") (pin "P$W1") (pinfunction "VDD_P$W1") (pintype "power_in"))
      (node (ref "U1") (pin "P$Y2") (pinfunction "VDDH_P$Y2") (pintype "power_in"))
    )
    (net (code "8") (name "ALERT") (class "Default")
      (node (ref "U1") (pin "P$J24") (pinfunction "P0.10/NFC2_P$J24") (pintype "bidirectional"))
      (node (ref "U3") (pin "5") (pinfunction "~{ALERT}_5") (pintype "output"))
    )
    (net (code "9") (name "D+") (class "Default")
      (node (ref "D3") (pin "4") (pinfunction "I/O2_2_4") (pintype "bidirectional"))
      (node (ref "U1") (pin "P$AD6") (pinfunction "D+_P$AD6") (pintype "bidirectional"))
    )
    (net (code "10") (name "D-") (class "Default")
      (node (ref "D3") (pin "6") (pinfunction "I/O1_2_6") (pintype "bidirectional"))
      (node (ref "U1") (pin "P$AD4") (pinfunction "D-_P$AD4") (pintype "bidirectional"))
    )
    (net (code "11") (name "DN") (class "Default")
      (node (ref "D3") (pin "1") (pinfunction "I/O1_1_1") (pintype "bidirectional"))
      (node (ref "J4") (pin "A7") (pinfunction "DN1_A7") (pintype "bidirectional"))
      (node (ref "J4") (pin "B7") (pinfunction "DN2_B7") (pintype "bidirectional"))
    )
    (net (code "12") (name "DP") (class "Default")
      (node (ref "D3") (pin "3") (pinfunction "I/O2_1_3") (pintype "bidirectional"))
      (node (ref "J4") (pin "A6") (pinfunction "DP1_A6") (pintype "bidirectional"))
      (node (ref "J4") (pin "B6") (pinfunction "DP2_B6") (pintype "bidirectional"))
    )
    (net (code "13") (name "EPD_3V3") (class "Default")
      (node (ref "C1-EP-DR") (pin "1") (pinfunction "1_1") (pintype "passive"))
      (node (ref "EPD_C5") (pin "1") (pinfunction "1_1") (pintype "passive"))
      (node (ref "J1") (pin "15") (pinfunction "15_15") (pintype "bidirectional"))
      (node (ref "J1") (pin "16") (pinfunction "16_16") (pintype "bidirectional"))
      (node (ref "L5") (pin "1") (pinfunction "1_1") (pintype "passive"))
      (node (ref "Q1") (pin "3") (pinfunction "D_3") (pintype "bidirectional"))
    )
    (net (code "14") (name "EPD_BUSY") (class "Default")
      (node (ref "J1") (pin "9") (pinfunction "9_9") (pintype "bidirectional"))
      (node (ref "U1") (pin "P$AD12") (pinfunction "P0.17_P$AD12") (pintype "bidirectional"))
    )
    (net (code "15") (name "EPD_CS") (class "Default")
      (node (ref "J1") (pin "12") (pinfunction "12_12") (pintype "bidirectional"))
      (node (ref "U1") (pin "P$K2") (pinfunction "P0.05/AIN3_P$K2") (pintype "bidirectional"))
    )
    (net (code "16") (name "EPD_DC") (class "Default")
      (node (ref "J1") (pin "11") (pinfunction "11_11") (pintype "bidirectional"))
      (node (ref "U1") (pin "P$AD10") (pinfunction "P0.15_P$AD10") (pintype "bidirectional"))
    )
    (net (code "17") (name "EPD_RST") (class "Default")
      (node (ref "J1") (pin "10") (pinfunction "10_10") (pintype "bidirectional"))
      (node (ref "U1") (pin "P$AC11") (pinfunction "P0.16_P$AC11") (pintype "bidirectional"))
    )
    (net (code "18") (name "GDR") (class "Default")
      (node (ref "J1") (pin "2") (pinfunction "2_2") (pintype "bidirectional"))
      (node (ref "Q3") (pin "1") (pinfunction "G_1") (pintype "bidirectional"))
      (node (ref "R2_EP_DR") (pin "2") (pinfunction "2_2") (pintype "bidirectional"))
    )
    (net (code "19") (name "GND") (class "Default")
      (node (ref "C1") (pin "2") (pinfunction "2_2") (pintype "passive"))
      (node (ref "C1-EP-DR") (pin "2") (pinfunction "2_2") (pintype "passive"))
      (node (ref "C10") (pin "2") (pinfunction "2_2") (pintype "passive"))
      (node (ref "C11") (pin "2") (pinfunction "2_2") (pintype "passive"))
      (node (ref "C12") (pin "2") (pinfunction "2_2") (pintype "passive"))
      (node (ref "C13") (pin "2") (pinfunction "2_2") (pintype "passive"))
      (node (ref "C14") (pin "2") (pinfunction "2_2") (pintype "passive"))
      (node (ref "C15") (pin "2") (pinfunction "2_2") (pintype "passive"))
      (node (ref "C16") (pin "2") (pinfunction "2_2") (pintype "passive"))
      (node (ref "C17") (pin "1") (pinfunction "1_1") (pintype "passive"))
      (node (ref "C18") (pin "1") (pinfunction "1_1") (pintype "passive"))
      (node (ref "C19") (pin "2") (pinfunction "2_2") (pintype "passive"))
      (node (ref "C2") (pin "2") (pinfunction "2_2") (pintype "passive"))
      (node (ref "C20") (pin "2") (pinfunction "2_2") (pintype "passive"))
      (node (ref "C21") (pin "2") (pinfunction "2_2") (pintype "passive"))
      (node (ref "C22") (pin "2") (pinfunction "2_2") (pintype "passive"))
      (node (ref "C23") (pin "1") (pinfunction "1_1") (pintype "passive"))
      (node (ref "C24") (pin "1") (pinfunction "1_1") (pintype "passive"))
      (node (ref "C25") (pin "2") (pinfunction "2_2") (pintype "passive"))
      (node (ref "C27") (pin "1") (pinfunction "1_1") (pintype "passive"))
      (node (ref "C29") (pin "1") (pinfunction "1_1") (pintype "passive"))
      (node (ref "C3") (pin "2") (pinfunction "2_2") (pintype "passive"))
      (node (ref "C30") (pin "1") (pinfunction "1_1") (pintype "passive"))
      (node (ref "C31") (pin "1") (pinfunction "1_1") (pintype "passive"))
      (node (ref "C32") (pin "2") (pinfunction "2_2") (pintype "passive"))
      (node (ref "C33") (pin "2") (pinfunction "2_2") (pintype "passive"))
      (node (ref "C34") (pin "1") (pinfunction "1_1") (pintype "passive"))
      (node (ref "C37") (pin "2") (pinfunction "2_2") (pintype "passive"))
      (node (ref "C38") (pin "2") (pinfunction "2_2") (pintype "passive"))
      (node (ref "C39") (pin "2") (pinfunction "2_2") (pintype "passive"))
      (node (ref "C4") (pin "2") (pinfunction "2_2") (pintype "passive"))
      (node (ref "C42") (pin "2") (pinfunction "2_2") (pintype "passive"))
      (node (ref "C43") (pin "2") (pinfunction "2_2") (pintype "passive"))
      (node (ref "C5") (pin "2") (pinfunction "2_2") (pintype "passive"))
      (node (ref "C6") (pin "2") (pinfunction "2_2") (pintype "passive"))
      (node (ref "C7") (pin "2") (pinfunction "2_2") (pintype "passive"))
      (node (ref "C8") (pin "2") (pinfunction "2_2") (pintype "passive"))
      (node (ref "C9") (pin "2") (pinfunction "2_2") (pintype "passive"))
      (node (ref "D3") (pin "2") (pinfunction "GND_2") (pintype "bidirectional"))
      (node (ref "D4") (pin "1") (pinfunction "K_1") (pintype "bidirectional"))
      (node (ref "EPD_C1") (pin "1") (pinfunction "1_1") (pintype "passive"))
      (node (ref "EPD_C10") (pin "1") (pinfunction "1_1") (pintype "passive"))
      (node (ref "EPD_C11") (pin "1") (pinfunction "1_1") (pintype "passive"))
      (node (ref "EPD_C12") (pin "1") (pinfunction "1_1") (pintype "passive"))
      (node (ref "EPD_C2") (pin "1") (pinfunction "1_1") (pintype "passive"))
      (node (ref "EPD_C5") (pin "2") (pinfunction "2_2") (pintype "passive"))
      (node (ref "EPD_C6") (pin "1") (pinfunction "1_1") (pintype "passive"))
      (node (ref "EPD_C7") (pin "1") (pinfunction "1_1") (pintype "passive"))
      (node (ref "EPD_C8") (pin "1") (pinfunction "1_1") (pintype "passive"))
      (node (ref "EPD_C9") (pin "1") (pinfunction "1_1") (pintype "passive"))
      (node (ref "IC1") (pin "D2") (pinfunction "GND_D2") (pintype "bidirectional"))
      (node (ref "IC2") (pin "B1") (pinfunction "IN/TRIG_B1") (pintype "bidirectional"))
      (node (ref "IC2") (pin "B3") (pinfunction "GND_B3") (pintype "bidirectional"))
      (node (ref "IC3") (pin "8") (pinfunction "GNDIO_8") (pintype "bidirectional"))
      (node (ref "IC3") (pin "9") (pinfunction "GND_9") (pintype "bidirectional"))
      (node (ref "IC9") (pin "B1") (pinfunction "VSEL_B1") (pintype "bidirectional"))
      (node (ref "IC9") (pin "C1") (pinfunction "AGND_C1") (pintype "bidirectional"))
      (node (ref "IC9") (pin "C2") (pinfunction "PGND_1_C2") (pintype "bidirectional"))
      (node (ref "IC9") (pin "C3") (pinfunction "PGND_2_C3") (pintype "bidirectional"))
      (node (ref "J1") (pin "17") (pinfunction "17_17") (pintype "bidirectional"))
      (node (ref "J1") (pin "8") (pinfunction "8_8") (pintype "bidirectional"))
      (node (ref "J1") (pin "MP1") (pinfunction "MP1_MP1") (pintype "bidirectional"))
      (node (ref "J1") (pin "MP2") (pinfunction "MP2_MP2") (pintype "bidirectional"))
      (node (ref "J2\\") (pin "3") (pinfunction "3_3") (pintype "bidirectional"))
      (node (ref "J2\\") (pin "5") (pinfunction "5_5") (pintype "bidirectional"))
      (node (ref "J4") (pin "A12_B1") (pinfunction "GND_A12_B1") (pintype "power_in"))
      (node (ref "J4") (pin "A1_B12") (pinfunction "GND_A1_B12") (pintype "power_in"))
      (node (ref "J4") (pin "SH1") (pinfunction "SHIELD_SH1") (pintype "passive"))
      (node (ref "J4") (pin "SH2") (pinfunction "SHIELD_SH2") (pintype "passive"))
      (node (ref "J4") (pin "SH3") (pinfunction "SHIELD_SH3") (pintype "passive"))
      (node (ref "J4") (pin "SH4") (pinfunction "SHIELD_SH4") (pintype "passive"))
      (node (ref "R1_USB") (pin "1") (pinfunction "1_1") (pintype "bidirectional"))
      (node (ref "R2_EP_DR") (pin "1") (pinfunction "1_1") (pintype "bidirectional"))
      (node (ref "R2_USB") (pin "2") (pinfunction "2_2") (pintype "bidirectional"))
      (node (ref "R3") (pin "2") (pinfunction "2_2") (pintype "bidirectional"))
      (node (ref "R9") (pin "1") (pinfunction "1_1") (pintype "bidirectional"))
      (node (ref "R_TYPE_SEL") (pin "1") (pinfunction "1_1") (pintype "bidirectional"))
      (node (ref "SJ1") (pin "1") (pinfunction "1_1") (pintype "passive"))
      (node (ref "SW_DN") (pin "1") (pinfunction "1_1") (pintype "passive"))
      (node (ref "SW_ENT") (pin "1") (pinfunction "1_1") (pintype "passive"))
      (node (ref "SW_UP") (pin "1") (pinfunction "1_1") (pintype "passive"))
      (node (ref "TP_BAT_GND") (pin "TP") (pinfunction "TP_TP") (pintype "input"))
      (node (ref "TP_GND") (pin "TP") (pinfunction "TP_TP") (pintype "input"))
      (node (ref "U1") (pin "P$74") (pinfunction "VSS_PAD_P$74") (pintype "bidirectional"))
      (node (ref "U1") (pin "P$75") (pinfunction "VSS_PAD_P$75") (pintype "bidirectional"))
      (node (ref "U1") (pin "P$76") (pinfunction "VSS_PAD_P$76") (pintype "bidirectional"))
      (node (ref "U1") (pin "P$77") (pinfunction "VSS_PAD_P$77") (pintype "bidirectional"))
      (node (ref "U1") (pin "P$78") (pinfunction "VSS_PAD_P$78") (pintype "bidirectional"))
      (node (ref "U1") (pin "P$79") (pinfunction "VSS_PAD_P$79") (pintype "bidirectional"))
      (node (ref "U1") (pin "P$80") (pinfunction "VSS_PAD_P$80") (pintype "bidirectional"))
      (node (ref "U1") (pin "P$81") (pinfunction "VSS_PAD_P$81") (pintype "bidirectional"))
      (node (ref "U1") (pin "P$82") (pinfunction "VSS_PAD_P$82") (pintype "bidirectional"))
      (node (ref "U1") (pin "P$83") (pinfunction "VSS_PAD_P$83") (pintype "bidirectional"))
      (node (ref "U1") (pin "P$84") (pinfunction "VSS_PAD_P$84") (pintype "bidirectional"))
      (node (ref "U1") (pin "P$85") (pinfunction "VSS_PAD_P$85") (pintype "bidirectional"))
      (node (ref "U1") (pin "P$86") (pinfunction "VSS_PAD_P$86") (pintype "bidirectional"))
      (node (ref "U1") (pin "P$87") (pinfunction "VSS_PAD_P$87") (pintype "bidirectional"))
      (node (ref "U1") (pin "P$88") (pinfunction "VSS_PAD_P$88") (pintype "bidirectional"))
      (node (ref "U1") (pin "P$89") (pinfunction "VSS_PAD_P$89") (pintype "bidirectional"))
      (node (ref "U1") (pin "P$90") (pinfunction "VSS_PAD_P$90") (pintype "bidirectional"))
      (node (ref "U1") (pin "P$B7") (pinfunction "VSS_P$B7") (pintype "power_in"))
      (node (ref "U1") (pin "P$F23") (pinfunction "VSS_PA_P$F23") (pintype "bidirectional"))
      (node (ref "U3") (pin "1") (pinfunction "CTG_1") (pintype "power_in"))
      (node (ref "U3") (pin "4") (pinfunction "GND_4") (pintype "power_in"))
      (node (ref "U3") (pin "6") (pinfunction "QSTRT_6") (pintype "input"))
      (node (ref "U3") (pin "9") (pinfunction "EP_9") (pintype "power_in"))
      (node (ref "X1") (pin "2") (pinfunction "2_2") (pintype "passive"))
      (node (ref "X1") (pin "4") (pinfunction "4_4") (pintype "passive"))
    )
    (net (code "20") (name "HAPTIC_EN") (class "Default")
      (node (ref "IC2") (pin "A1") (pinfunction "EN_A1") (pintype "bidirectional"))
      (node (ref "U1") (pin "P$U1") (pinfunction "P0.12_P$U1") (pintype "bidirectional"))
    )
    (net (code "21") (name "IMU_INT1") (class "Default")
      (node (ref "IC3") (pin "5") (pinfunction "INT1_5") (pintype "bidirectional"))
      (node (ref "U1") (pin "P$N1") (pinfunction "P0.08_P$N1") (pintype "bidirectional"))
    )
    (net (code "22") (name "IMU_INT2") (class "Default")
      (node (ref "IC3") (pin "6") (pinfunction "INT2_6") (pintype "bidirectional"))
      (node (ref "U1") (pin "P$P2") (pinfunction "P1.08_P$P2") (pintype "bidirectional"))
    )
    (net (code "23") (name "LX1") (class "Default")
      (node (ref "IC9") (pin "B2") (pinfunction "SW1_1_B2") (pintype "bidirectional"))
      (node (ref "L7") (pin "1") (pinfunction "1_1") (pintype "bidirectional"))
    )
    (net (code "24") (name "LX2") (class "Default")
      (node (ref "IC9") (pin "D2") (pinfunction "SW2_1_D2") (pintype "bidirectional"))
      (node (ref "IC9") (pin "D3") (pinfunction "SW2_2_D3") (pintype "bidirectional"))
      (node (ref "L7") (pin "2") (pinfunction "2_2") (pintype "bidirectional"))
    )
    (net (code "25") (name "MOSI") (class "Default")
      (node (ref "J1") (pin "14") (pinfunction "14_14") (pintype "bidirectional"))
      (node (ref "U1") (pin "P$B13") (pinfunction "P0.03/AIN1_P$B13") (pintype "bidirectional"))
    )
    (net (code "26") (name "N$19") (class "Default")
      (node (ref "R_PWR_EPD") (pin "2") (pinfunction "2_2") (pintype "bidirectional"))
    )
    (net (code "27") (name "Net-(D2-K)") (class "Default")
      (node (ref "C2-EP-DR") (pin "1") (pinfunction "1_1") (pintype "passive"))
      (node (ref "D2") (pin "1") (pinfunction "K_1") (pintype "bidirectional"))
      (node (ref "D4") (pin "2") (pinfunction "A_2") (pintype "bidirectional"))
    )
    (net (code "28") (name "Net-(D5-A)") (class "Default")
      (node (ref "C2-EP-DR") (pin "2") (pinfunction "2_2") (pintype "passive"))
      (node (ref "D5") (pin "2") (pinfunction "A_2") (pintype "bidirectional"))
      (node (ref "L5") (pin "2") (pinfunction "2_2") (pintype "passive"))
      (node (ref "Q3") (pin "3") (pinfunction "D_3") (pintype "bidirectional"))
    )
    (net (code "29") (name "Net-(EPD_C1-Pad2)") (class "Default")
      (node (ref "EPD_C1") (pin "2") (pinfunction "2_2") (pintype "passive"))
      (node (ref "J1") (pin "5") (pinfunction "5_5") (pintype "bidirectional"))
    )
    (net (code "30") (name "Net-(EPD_C2-Pad2)") (class "Default")
      (node (ref "EPD_C2") (pin "2") (pinfunction "2_2") (pintype "passive"))
      (node (ref "J1") (pin "4") (pinfunction "4_4") (pintype "bidirectional"))
    )
    (net (code "31") (name "Net-(EPD_C6-Pad2)") (class "Default")
      (node (ref "EPD_C6") (pin "2") (pinfunction "2_2") (pintype "passive"))
      (node (ref "J1") (pin "18") (pinfunction "18_18") (pintype "bidirectional"))
    )
    (net (code "32") (name "Net-(EPD_C7-Pad2)") (class "Default")
      (node (ref "EPD_C7") (pin "2") (pinfunction "2_2") (pintype "passive"))
      (node (ref "J1") (pin "19") (pinfunction "19_19") (pintype "bidirectional"))
    )
    (net (code "33") (name "Net-(EPD_C8-Pad2)") (class "Default")
      (node (ref "EPD_C8") (pin "2") (pinfunction "2_2") (pintype "passive"))
      (node (ref "J1") (pin "20") (pinfunction "20_20") (pintype "bidirectional"))
    )
    (net (code "34") (name "Net-(EPD_C10-Pad2)") (class "Default")
      (node (ref "EPD_C10") (pin "2") (pinfunction "2_2") (pintype "passive"))
      (node (ref "J1") (pin "22") (pinfunction "22_22") (pintype "bidirectional"))
    )
    (net (code "35") (name "Net-(EPD_C12-Pad2)") (class "Default")
      (node (ref "EPD_C12") (pin "2") (pinfunction "2_2") (pintype "passive"))
      (node (ref "J1") (pin "24") (pinfunction "24_24") (pintype "bidirectional"))
    )
    (net (code "36") (name "Net-(IC1-TS{slash}MR)") (class "Default")
      (node (ref "IC1") (pin "D1") (pinfunction "TS/MR_D1") (pintype "bidirectional"))
      (node (ref "R9") (pin "2") (pinfunction "2_2") (pintype "bidirectional"))
    )
    (net (code "37") (name "Net-(IC2-REG)") (class "Default")
      (node (ref "C32") (pin "1") (pinfunction "1_1") (pintype "passive"))
      (node (ref "IC2") (pin "A2") (pinfunction "REG_A2") (pintype "bidirectional"))
    )
    (net (code "38") (name "Net-(IC3-SDO)") (class "Default")
      (node (ref "IC3") (pin "1") (pinfunction "SDO_1") (pintype "bidirectional"))
      (node (ref "R3") (pin "1") (pinfunction "1_1") (pintype "bidirectional"))
    )
    (net (code "39") (name "Net-(IC9-SCL)") (class "Default")
      (node (ref "IC9") (pin "D1") (pinfunction "SCL_D1") (pintype "bidirectional"))
      (node (ref "R4") (pin "1") (pinfunction "1_1") (pintype "bidirectional"))
    )
    (net (code "40") (name "Net-(IC9-SDA)") (class "Default")
      (node (ref "IC9") (pin "E1") (pinfunction "SDA_E1") (pintype "bidirectional"))
      (node (ref "R2") (pin "1") (pinfunction "1_1") (pintype "bidirectional"))
    )
    (net (code "41") (name "Net-(J4-CC1)") (class "Default")
      (node (ref "J4") (pin "A5") (pinfunction "CC1_A5") (pintype "bidirectional"))
      (node (ref "R1_USB") (pin "2") (pinfunction "2_2") (pintype "bidirectional"))
    )
    (net (code "42") (name "Net-(J4-CC2)") (class "Default")
      (node (ref "J4") (pin "B5") (pinfunction "CC2_B5") (pintype "bidirectional"))
      (node (ref "R2_USB") (pin "1") (pinfunction "1_1") (pintype "bidirectional"))
    )
    (net (code "43") (name "Net-(L2-Pad2)") (class "Default")
      (node (ref "L2") (pin "2") (pinfunction "2_2") (pintype "passive"))
      (node (ref "L3") (pin "1") (pinfunction "1_1") (pintype "passive"))
    )
    (net (code "44") (name "Net-(R1_EP_DR-Pad1)") (class "Default")
      (node (ref "R1_EP_DR") (pin "1") (pinfunction "1_1") (pintype "bidirectional"))
      (node (ref "R_TYPE_SEL") (pin "2") (pinfunction "2_2") (pintype "bidirectional"))
      (node (ref "SJ1") (pin "2") (pinfunction "2_2") (pintype "passive"))
    )
    (net (code "45") (name "Net-(U1-ANT)") (class "Default")
      (node (ref "C3") (pin "1") (pinfunction "1_1") (pintype "passive"))
      (node (ref "L1") (pin "1") (pinfunction "1_1") (pintype "passive"))
      (node (ref "U1") (pin "P$H23") (pinfunction "ANT_P$H23") (pintype "bidirectional"))
    )
    (net (code "46") (name "Net-(U1-DCC)") (class "Default")
      (node (ref "L2") (pin "1") (pinfunction "1_1") (pintype "passive"))
      (node (ref "U1") (pin "P$B3") (pinfunction "DCC_P$B3") (pintype "output"))
    )
    (net (code "47") (name "Net-(U1-DEC2)") (class "Default")
      (node (ref "C13") (pin "1") (pinfunction "1_1") (pintype "passive"))
      (node (ref "U1") (pin "P$A18") (pinfunction "DEC2_P$A18") (pintype "bidirectional"))
    )
    (net (code "48") (name "Net-(U1-DEC3V3)") (class "Default")
      (node (ref "C20") (pin "1") (pinfunction "1_1") (pintype "passive"))
      (node (ref "U1") (pin "P$AC5") (pinfunction "DEC3V3_P$AC5") (pintype "bidirectional"))
    )
    (net (code "49") (name "Net-(U1-DEC5)") (class "Default")
      (node (ref "C9") (pin "1") (pinfunction "1_1") (pintype "passive"))
      (node (ref "U1") (pin "P$N24") (pinfunction "DEC5_P$N24") (pintype "bidirectional"))
    )
    (net (code "50") (name "Net-(U1-XC1)") (class "Default")
      (node (ref "C1") (pin "1") (pinfunction "1_1") (pintype "passive"))
      (node (ref "U1") (pin "P$B24") (pinfunction "XC1_P$B24") (pintype "input"))
      (node (ref "X1") (pin "1") (pinfunction "1_1") (pintype "passive"))
    )
    (net (code "51") (name "Net-(U1-XC2)") (class "Default")
      (node (ref "C2") (pin "1") (pinfunction "1_1") (pintype "passive"))
      (node (ref "U1") (pin "P$A23") (pinfunction "XC2_P$A23") (pintype "output"))
      (node (ref "X1") (pin "3") (pinfunction "3_3") (pintype "passive"))
    )
    (net (code "52") (name "OUT+") (class "Default")
      (node (ref "IC2") (pin "A3") (pinfunction "OUT+_A3") (pintype "bidirectional"))
      (node (ref "TP1") (pin "TP") (pinfunction "TP_TP") (pintype "input"))
    )
    (net (code "53") (name "OUT-") (class "Default")
      (node (ref "IC2") (pin "C3") (pinfunction "OUT-_C3") (pintype "bidirectional"))
      (node (ref "TP2") (pin "TP") (pinfunction "TP_TP") (pintype "input"))
    )
    (net (code "54") (name "P0.04") (class "Default")
      (node (ref "U1") (pin "P$J1") (pinfunction "P0.04/AIN2_P$J1") (pintype "bidirectional"))
    )
    (net (code "55") (name "P0.09") (class "Default")
      (node (ref "U1") (pin "P$L24") (pinfunction "P0.09/NFC1_P$L24") (pintype "bidirectional"))
    )
    (net (code "56") (name "P0.13") (class "Default")
      (node (ref "C30") (pin "2") (pinfunction "2_2") (pintype "passive"))
      (node (ref "R5") (pin "1") (pinfunction "1_1") (pintype "bidirectional"))
      (node (ref "SW_UP") (pin "2") (pinfunction "2_2") (pintype "passive"))
      (node (ref "U1") (pin "P$AD8") (pinfunction "P0.13_P$AD8") (pintype "bidirectional"))
    )
    (net (code "57") (name "P0.14") (class "Default")
      (node (ref "C31") (pin "2") (pinfunction "2_2") (pintype "passive"))
      (node (ref "R8") (pin "1") (pinfunction "1_1") (pintype "bidirectional"))
      (node (ref "SW_ENT") (pin "2") (pinfunction "2_2") (pintype "passive"))
      (node (ref "U1") (pin "P$AC9") (pinfunction "P0.14_P$AC9") (pintype "bidirectional"))
    )
    (net (code "58") (name "P0.19") (class "Default")
      (node (ref "U1") (pin "P$AC15") (pinfunction "P0.19_P$AC15") (pintype "bidirectional"))
    )
    (net (code "59") (name "P0.20") (class "Default")
      (node (ref "U1") (pin "P$AD16") (pinfunction "P0.20_P$AD16") (pintype "bidirectional"))
    )
    (net (code "60") (name "P0.21") (class "Default")
      (node (ref "U1") (pin "P$AC17") (pinfunction "P0.21_P$AC17") (pintype "bidirectional"))
    )
    (net (code "61") (name "P0.22") (class "Default")
      (node (ref "U1") (pin "P$AD18") (pinfunction "P0.22_P$AD18") (pintype "bidirectional"))
    )
    (net (code "62") (name "P0.23") (class "Default")
      (node (ref "U1") (pin "P$AC19") (pinfunction "P0.23_P$AC19") (pintype "bidirectional"))
    )
    (net (code "63") (name "P0.24") (class "Default")
      (node (ref "U1") (pin "P$AD20") (pinfunction "P0.24_P$AD20") (pintype "bidirectional"))
    )
    (net (code "64") (name "P0.25") (class "Default")
      (node (ref "U1") (pin "P$AC21") (pinfunction "P0.25_P$AC21") (pintype "bidirectional"))
    )
    (net (code "65") (name "P0.26") (class "Default")
      (node (ref "U1") (pin "P$G1") (pinfunction "P0.26_P$G1") (pintype "bidirectional"))
    )
    (net (code "66") (name "P0.27") (class "Default")
      (node (ref "U1") (pin "P$H2") (pinfunction "P0.27_P$H2") (pintype "bidirectional"))
    )
    (net (code "67") (name "P0.28") (class "Default")
      (node (ref "U1") (pin "P$B11") (pinfunction "P0.28/AIN4_P$B11") (pintype "bidirectional"))
    )
    (net (code "68") (name "P0.29") (class "Default")
      (node (ref "U1") (pin "P$A10") (pinfunction "P0.29/AIN5_P$A10") (pintype "bidirectional"))
    )
    (net (code "69") (name "P0.30") (class "Default")
      (node (ref "U1") (pin "P$B9") (pinfunction "P0.30/AIN6_P$B9") (pintype "bidirectional"))
    )
    (net (code "70") (name "P0.31") (class "Default")
      (node (ref "U1") (pin "P$A8") (pinfunction "P0.31/AIN7_P$A8") (pintype "bidirectional"))
    )
    (net (code "71") (name "P1.01") (class "Default")
      (node (ref "Q1") (pin "1") (pinfunction "G_1") (pintype "bidirectional"))
      (node (ref "R_PWR_EPD") (pin "1") (pinfunction "1_1") (pintype "bidirectional"))
      (node (ref "U1") (pin "P$Y23") (pinfunction "P1.01_P$Y23") (pintype "bidirectional"))
    )
    (net (code "72") (name "P1.02") (class "Default")
      (node (ref "C29") (pin "2") (pinfunction "2_2") (pintype "passive"))
      (node (ref "R7") (pin "1") (pinfunction "1_1") (pintype "bidirectional"))
      (node (ref "SW_DN") (pin "2") (pinfunction "2_2") (pintype "passive"))
      (node (ref "U1") (pin "P$W24") (pinfunction "P1.02_P$W24") (pintype "bidirectional"))
    )
    (net (code "73") (name "P1.03") (class "Default")
      (node (ref "U1") (pin "P$V23") (pinfunction "P1.03_P$V23") (pintype "bidirectional"))
    )
    (net (code "74") (name "P1.04") (class "Default")
      (node (ref "U1") (pin "P$U24") (pinfunction "P1.04_P$U24") (pintype "bidirectional"))
    )
    (net (code "75") (name "P1.05") (class "Default")
      (node (ref "U1") (pin "P$T23") (pinfunction "P1.05_P$T23") (pintype "bidirectional"))
    )
    (net (code "76") (name "P1.06") (class "Default")
      (node (ref "U1") (pin "P$R24") (pinfunction "P1.06_P$R24") (pintype "bidirectional"))
    )
    (net (code "77") (name "P1.07") (class "Default")
      (node (ref "U1") (pin "P$P23") (pinfunction "P1.07_P$P23") (pintype "bidirectional"))
    )
    (net (code "78") (name "P1.09") (class "Default")
      (node (ref "U1") (pin "P$R1") (pinfunction "P1.09_P$R1") (pintype "bidirectional"))
    )
    (net (code "79") (name "P1.10") (class "Default")
      (node (ref "U1") (pin "P$A20") (pinfunction "P1.10_P$A20") (pintype "bidirectional"))
    )
    (net (code "80") (name "P1.11") (class "Default")
      (node (ref "U1") (pin "P$B19") (pinfunction "P1.11_P$B19") (pintype "bidirectional"))
    )
    (net (code "81") (name "P1.12") (class "Default")
      (node (ref "U1") (pin "P$B17") (pinfunction "P1.12_P$B17") (pintype "bidirectional"))
    )
    (net (code "82") (name "P1.13") (class "Default")
      (node (ref "U1") (pin "P$A16") (pinfunction "P1.13_P$A16") (pintype "bidirectional"))
    )
    (net (code "83") (name "P1.14") (class "Default")
      (node (ref "U1") (pin "P$B15") (pinfunction "P1.14_P$B15") (pintype "bidirectional"))
    )
    (net (code "84") (name "P1.15") (class "Default")
      (node (ref "U1") (pin "P$A14") (pinfunction "P1.15_P$A14") (pintype "bidirectional"))
    )
    (net (code "85") (name "PMIC_INT") (class "Default")
      (node (ref "IC1") (pin "A1") (pinfunction "~{INT}_A1") (pintype "bidirectional"))
      (node (ref "U1") (pin "P$T2") (pinfunction "P0.11_P$T2") (pintype "bidirectional"))
    )
    (net (code "86") (name "PREVGH") (class "Default")
      (node (ref "D5") (pin "1") (pinfunction "K_1") (pintype "bidirectional"))
      (node (ref "EPD_C9") (pin "2") (pinfunction "2_2") (pintype "passive"))
      (node (ref "J1") (pin "21") (pinfunction "21_21") (pintype "bidirectional"))
    )
    (net (code "87") (name "PREVGL") (class "Default")
      (node (ref "D2") (pin "2") (pinfunction "A_2") (pintype "bidirectional"))
      (node (ref "EPD_C11") (pin "2") (pinfunction "2_2") (pintype "passive"))
      (node (ref "J1") (pin "23") (pinfunction "23_23") (pintype "bidirectional"))
    )
    (net (code "88") (name "RESE") (class "Default")
      (node (ref "J1") (pin "3") (pinfunction "3_3") (pintype "bidirectional"))
      (node (ref "Q3") (pin "2") (pinfunction "S_2") (pintype "bidirectional"))
      (node (ref "R1_EP_DR") (pin "2") (pinfunction "2_2") (pintype "bidirectional"))
    )
    (net (code "89") (name "RESET") (class "Default")
      (node (ref "J2\\") (pin "6") (pinfunction "6_6") (pintype "bidirectional"))
      (node (ref "TP_RESET") (pin "TP") (pinfunction "TP_TP") (pintype "input"))
      (node (ref "U1") (pin "P$AC13") (pinfunction "P0.18/RESET_P$AC13") (pintype "bidirectional"))
    )
    (net (code "90") (name "SCK") (class "Default")
      (node (ref "J1") (pin "13") (pinfunction "13_13") (pintype "bidirectional"))
      (node (ref "U1") (pin "P$A12") (pinfunction "P0.02/AIN0_P$A12") (pintype "bidirectional"))
    )
    (net (code "91") (name "SCL") (class "Default")
      (node (ref "IC1") (pin "B1") (pinfunction "SCL_B1") (pintype "bidirectional"))
      (node (ref "IC2") (pin "C1") (pinfunction "SCL_C1") (pintype "bidirectional"))
      (node (ref "IC3") (pin "12") (pinfunction "SCX_12") (pintype "bidirectional"))
      (node (ref "R17") (pin "2") (pinfunction "2_2") (pintype "bidirectional"))
      (node (ref "R4") (pin "2") (pinfunction "2_2") (pintype "bidirectional"))
      (node (ref "TP_SCL") (pin "TP") (pinfunction "TP_TP") (pintype "input"))
      (node (ref "U1") (pin "P$M2") (pinfunction "P0.07_P$M2") (pintype "bidirectional"))
      (node (ref "U3") (pin "7") (pinfunction "SCL_7") (pintype "input"))
    )
    (net (code "92") (name "SDA") (class "Default")
      (node (ref "IC1") (pin "C1") (pinfunction "SDA_C1") (pintype "bidirectional"))
      (node (ref "IC2") (pin "B2") (pinfunction "SDA_B2") (pintype "bidirectional"))
      (node (ref "IC3") (pin "2") (pinfunction "SDX_2") (pintype "bidirectional"))
      (node (ref "R18") (pin "2") (pinfunction "2_2") (pintype "bidirectional"))
      (node (ref "R2") (pin "2") (pinfunction "2_2") (pintype "bidirectional"))
      (node (ref "TP_SDA") (pin "TP") (pinfunction "TP_TP") (pintype "input"))
      (node (ref "U1") (pin "P$L1") (pinfunction "P0.06_P$L1") (pintype "bidirectional"))
      (node (ref "U3") (pin "8") (pinfunction "SDA_8") (pintype "bidirectional"))
    )
    (net (code "93") (name "SWDCLK") (class "Default")
      (node (ref "J2\\") (pin "4") (pinfunction "4_4") (pintype "bidirectional"))
      (node (ref "U1") (pin "P$AA24") (pinfunction "SWDCLK_P$AA24") (pintype "input"))
      (node (ref "WP_SWDCLK") (pin "TP") (pinfunction "TP_TP") (pintype "input"))
    )
    (net (code "94") (name "SWDIO") (class "Default")
      (node (ref "J2\\") (pin "2") (pinfunction "2_2") (pintype "bidirectional"))
      (node (ref "TP_SWDIO") (pin "TP") (pinfunction "TP_TP") (pintype "input"))
      (node (ref "U1") (pin "P$AC24") (pinfunction "SWDIO_P$AC24") (pintype "bidirectional"))
    )
    (net (code "95") (name "SWO") (class "Default")
      (node (ref "TP_SWO") (pin "TP") (pinfunction "TP_TP") (pintype "input"))
      (node (ref "U1") (pin "P$AD22") (pinfunction "P1.00_P$AD22") (pintype "bidirectional"))
    )
    (net (code "96") (name "VBAT") (class "Default")
      (node (ref "C27") (pin "2") (pinfunction "2_2") (pintype "passive"))
      (node (ref "C37") (pin "1") (pinfunction "1_1") (pintype "passive"))
      (node (ref "IC1") (pin "C2") (pinfunction "BAT_C2") (pintype "bidirectional"))
      (node (ref "TP_VBAT") (pin "TP") (pinfunction "TP_TP") (pintype "input"))
      (node (ref "U3") (pin "2") (pinfunction "CELL_2") (pintype "power_in"))
      (node (ref "U3") (pin "3") (pinfunction "VDD_3") (pintype "power_in"))
    )
    (net (code "97") (name "VBUS") (class "Default")
      (node (ref "C21") (pin "1") (pinfunction "1_1") (pintype "passive"))
      (node (ref "C38") (pin "1") (pinfunction "1_1") (pintype "passive"))
      (node (ref "C42") (pin "1") (pinfunction "1_1") (pintype "passive"))
      (node (ref "C43") (pin "1") (pinfunction "1_1") (pintype "passive"))
      (node (ref "D3") (pin "5") (pinfunction "VBUS_5") (pintype "bidirectional"))
      (node (ref "IC1") (pin "A2") (pinfunction "IN_A2") (pintype "bidirectional"))
      (node (ref "J4") (pin "A4_B9") (pinfunction "VBUS_A4_B9") (pintype "power_in"))
      (node (ref "J4") (pin "A9_B4") (pinfunction "VBUS_A9_B4") (pintype "power_in"))
      (node (ref "U1") (pin "P$AD2") (pinfunction "VBUS_P$AD2") (pintype "power_in"))
    )
    (net (code "98") (name "VREG") (class "Default")
      (node (ref "C23") (pin "2") (pinfunction "2_2") (pintype "passive"))
      (node (ref "C24") (pin "2") (pinfunction "2_2") (pintype "passive"))
      (node (ref "C39") (pin "1") (pinfunction "1_1") (pintype "passive"))
      (node (ref "IC1") (pin "B2") (pinfunction "SYS_B2") (pintype "bidirectional"))
      (node (ref "IC9") (pin "A1") (pinfunction "EN_A1") (pintype "bidirectional"))
      (node (ref "IC9") (pin "A2") (pinfunction "VIN_1_A2") (pintype "bidirectional"))
      (node (ref "IC9") (pin "A3") (pinfunction "VIN_2_A3") (pintype "bidirectional"))
      (node (ref "TP_VREG") (pin "TP") (pinfunction "TP_TP") (pintype "input"))
    )
    (net (code "99") (name "unconnected-(ANT1-NC-Pad2)") (class "Default")
      (node (ref "ANT1") (pin "2") (pinfunction "NC_2") (pintype "no_connect"))
    )
    (net (code "100") (name "unconnected-(IC3-ASCL-Pad11)") (class "Default")
      (node (ref "IC3") (pin "11") (pinfunction "ASCL_11") (pintype "bidirectional"))
    )
    (net (code "101") (name "unconnected-(IC3-ASDA-Pad4)") (class "Default")
      (node (ref "IC3") (pin "4") (pinfunction "ASDA_4") (pintype "bidirectional"))
    )
    (net (code "102") (name "unconnected-(IC9-SW1_2-PadB3)") (class "Default")
      (node (ref "IC9") (pin "B3") (pinfunction "SW1_2_B3") (pintype "bidirectional"))
    )
    (net (code "103") (name "unconnected-(J1-Pad1)") (class "Default")
      (node (ref "J1") (pin "1") (pinfunction "1_1") (pintype "bidirectional"))
    )
    (net (code "104") (name "unconnected-(J1-Pad6)") (class "Default")
      (node (ref "J1") (pin "6") (pinfunction "6_6") (pintype "bidirectional"))
    )
    (net (code "105") (name "unconnected-(J1-Pad7)") (class "Default")
      (node (ref "J1") (pin "7") (pinfunction "7_7") (pintype "bidirectional"))
    )
    (net (code "106") (name "unconnected-(J4-SBU1-PadA8)") (class "Default")
      (node (ref "J4") (pin "A8") (pinfunction "SBU1_A8") (pintype "bidirectional"))
    )
    (net (code "107") (name "unconnected-(J4-SBU2-PadB8)") (class "Default")
      (node (ref "J4") (pin "B8") (pinfunction "SBU2_B8") (pintype "bidirectional"))
    )
    (net (code "108") (name "unconnected-(U1-DCCH-PadP$AB2)") (class "Default")
      (node (ref "U1") (pin "P$AB2") (pinfunction "DCCH_P$AB2") (pintype "bidirectional"))
    )
  )
)
